# alim.net
KiCad netlist of a schematic drawn in EAGLE
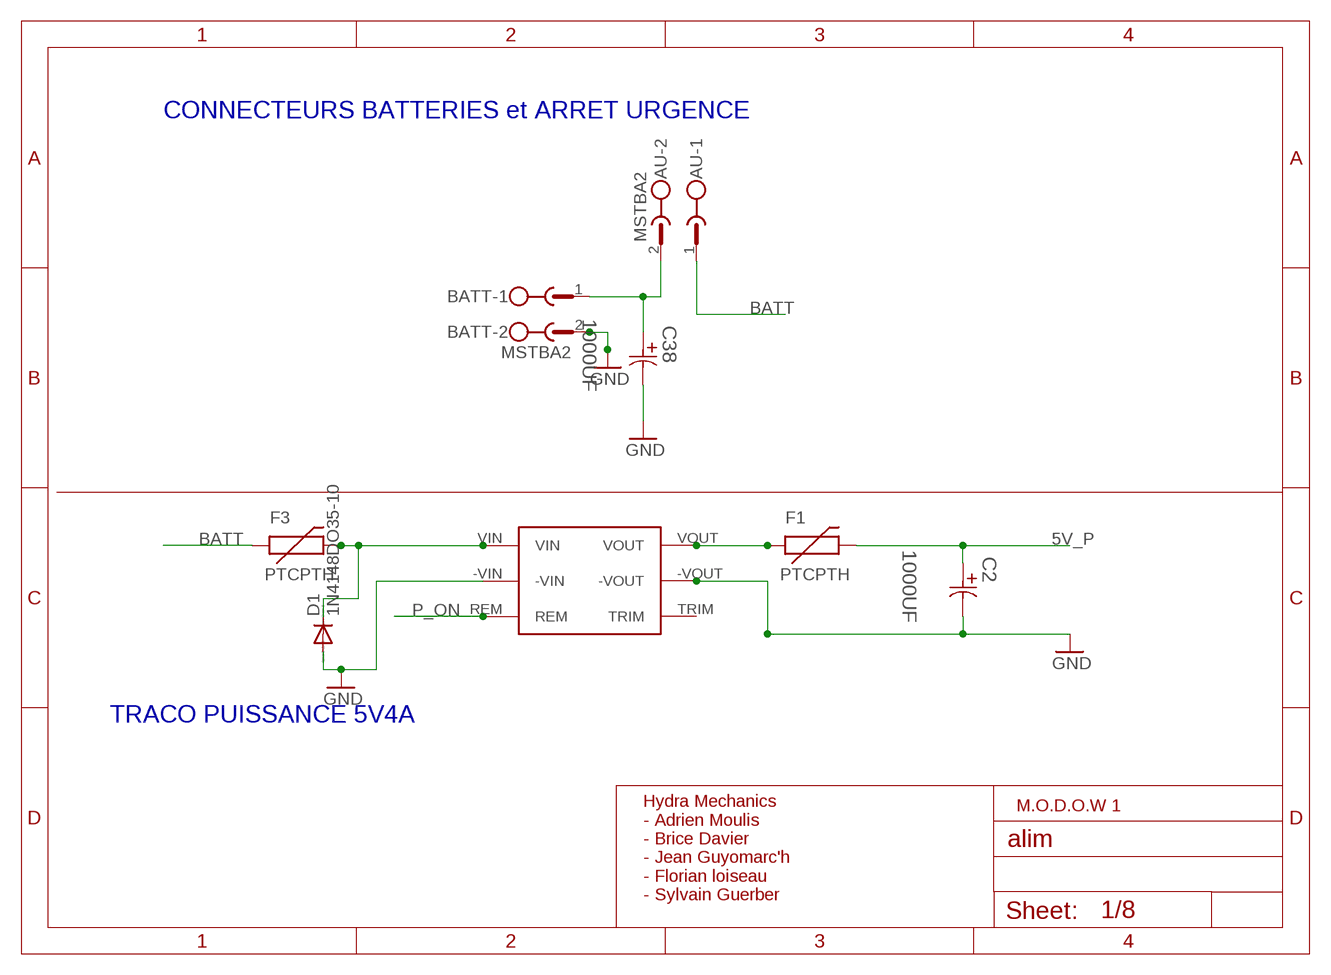
[diagram p0: schematic, sheet 1]
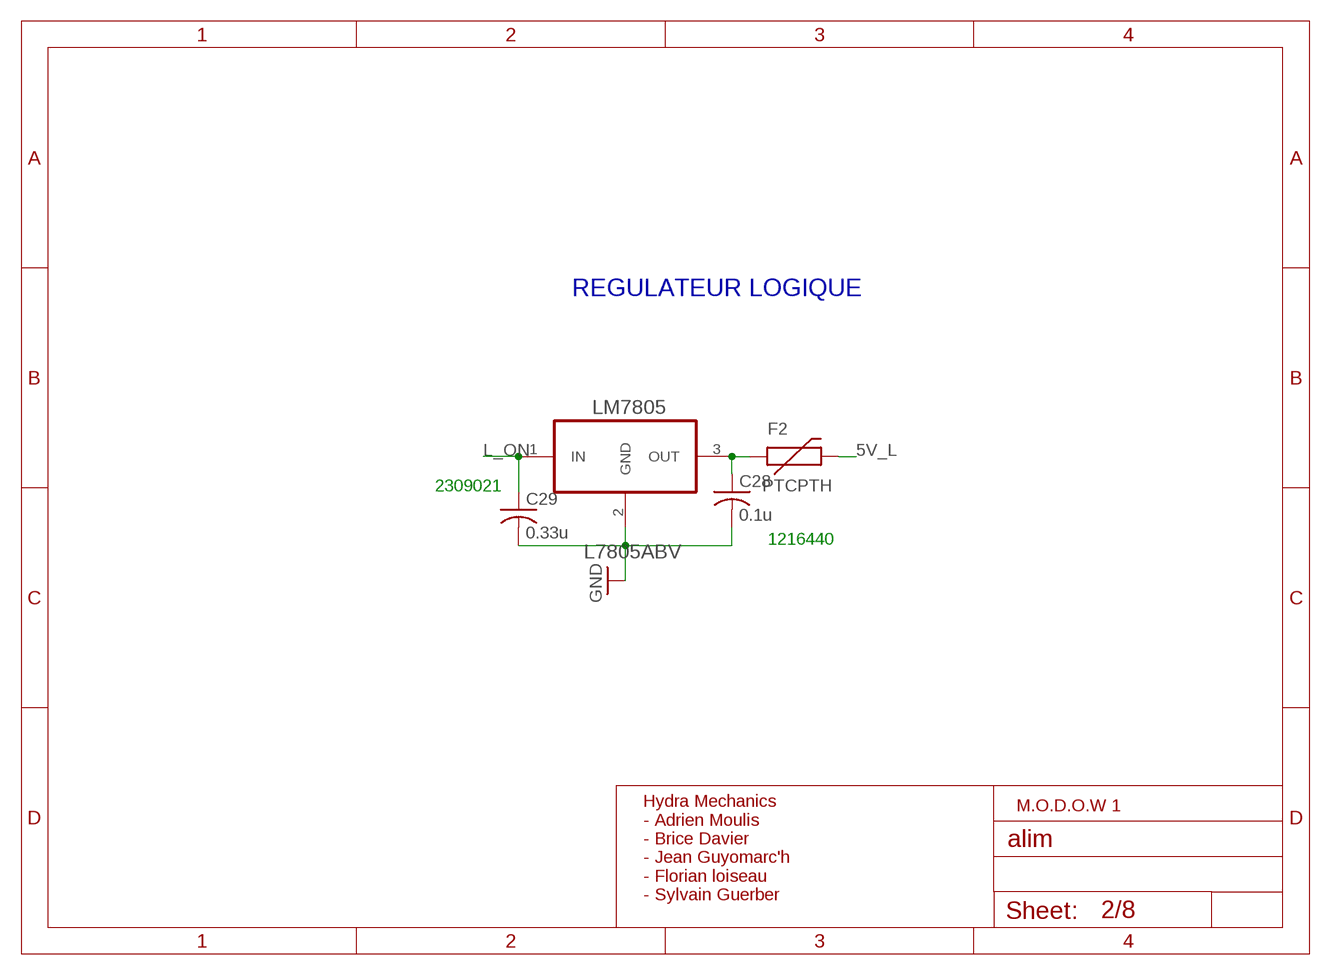
[diagram p1: schematic, sheet 2]
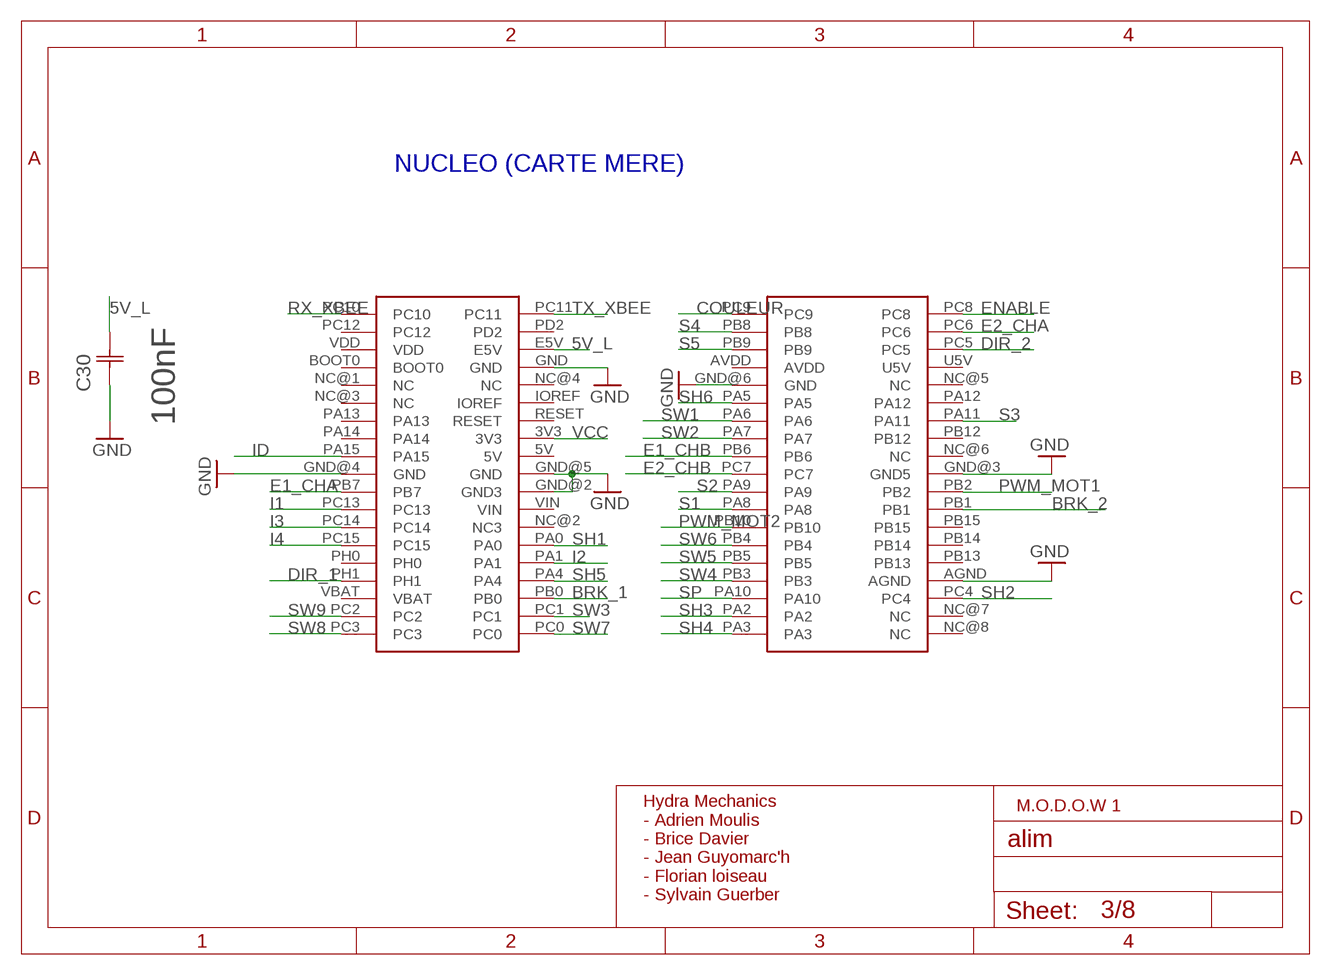
[diagram p2: schematic, sheet 3]
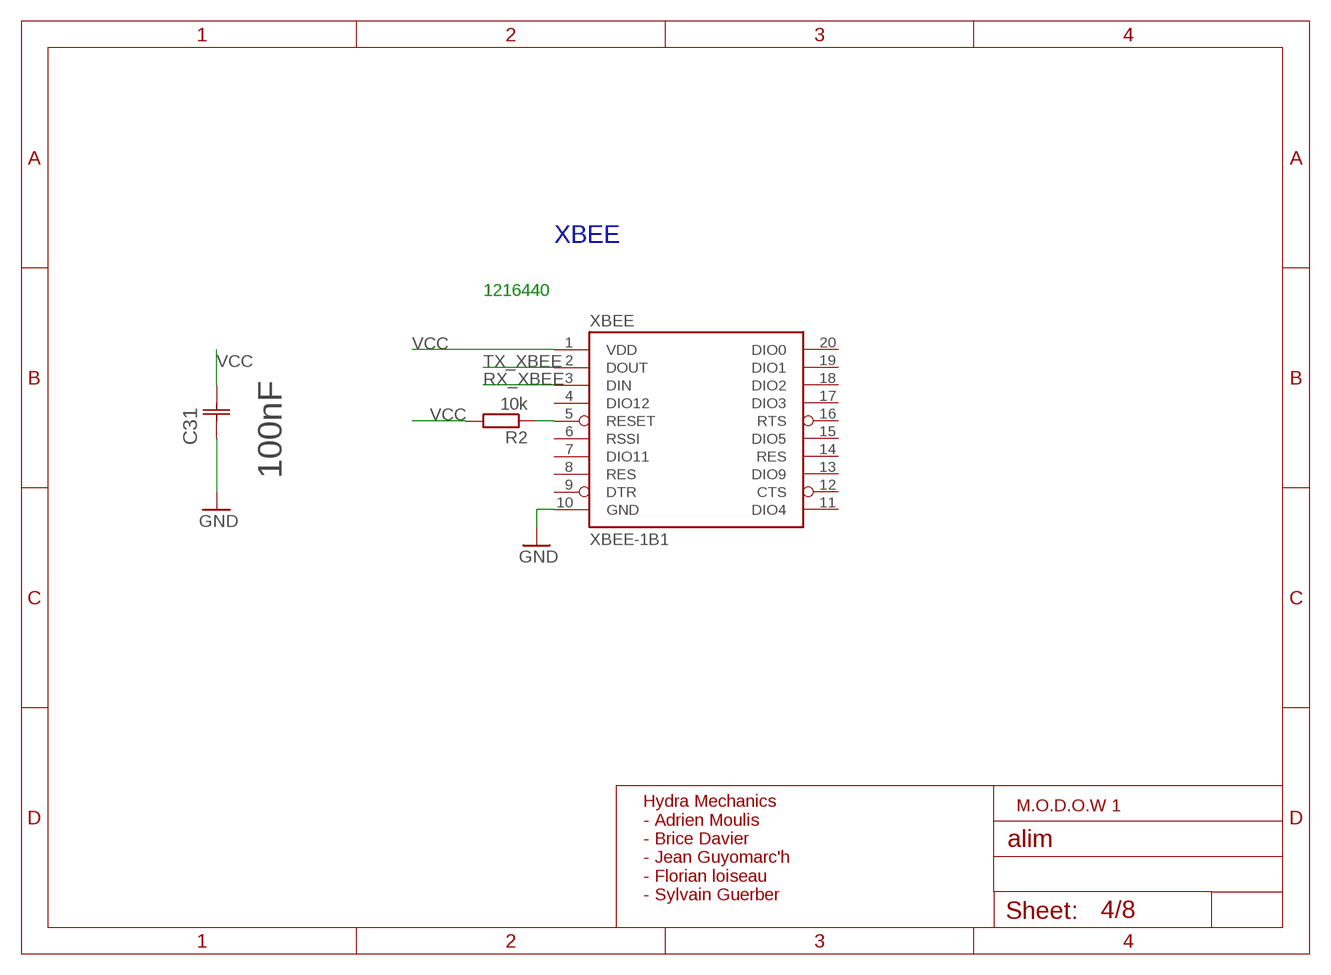
[diagram p3: schematic, sheet 4]
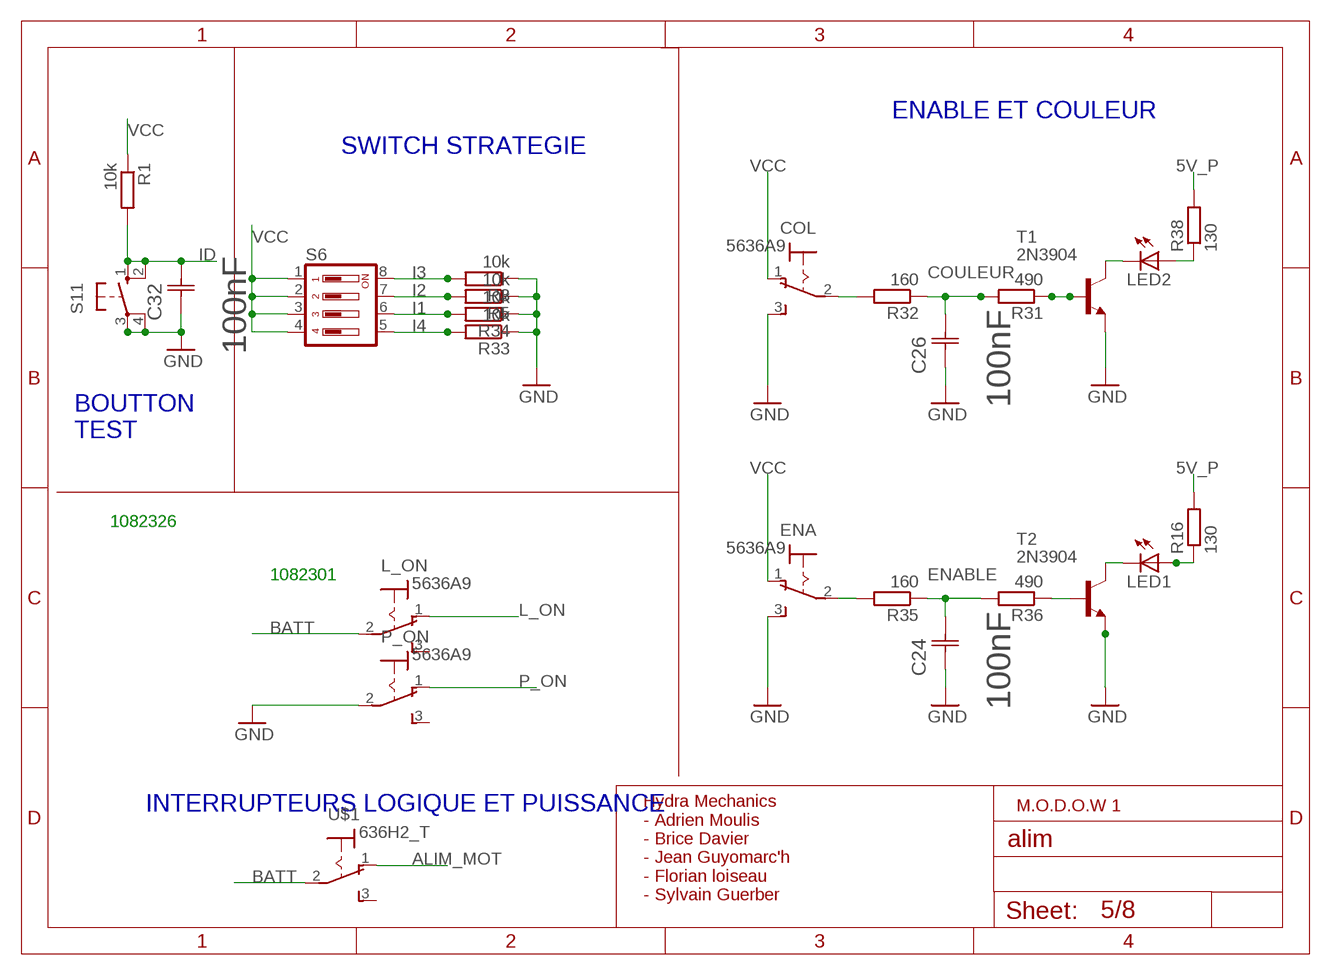
[diagram p4: schematic, sheet 5]
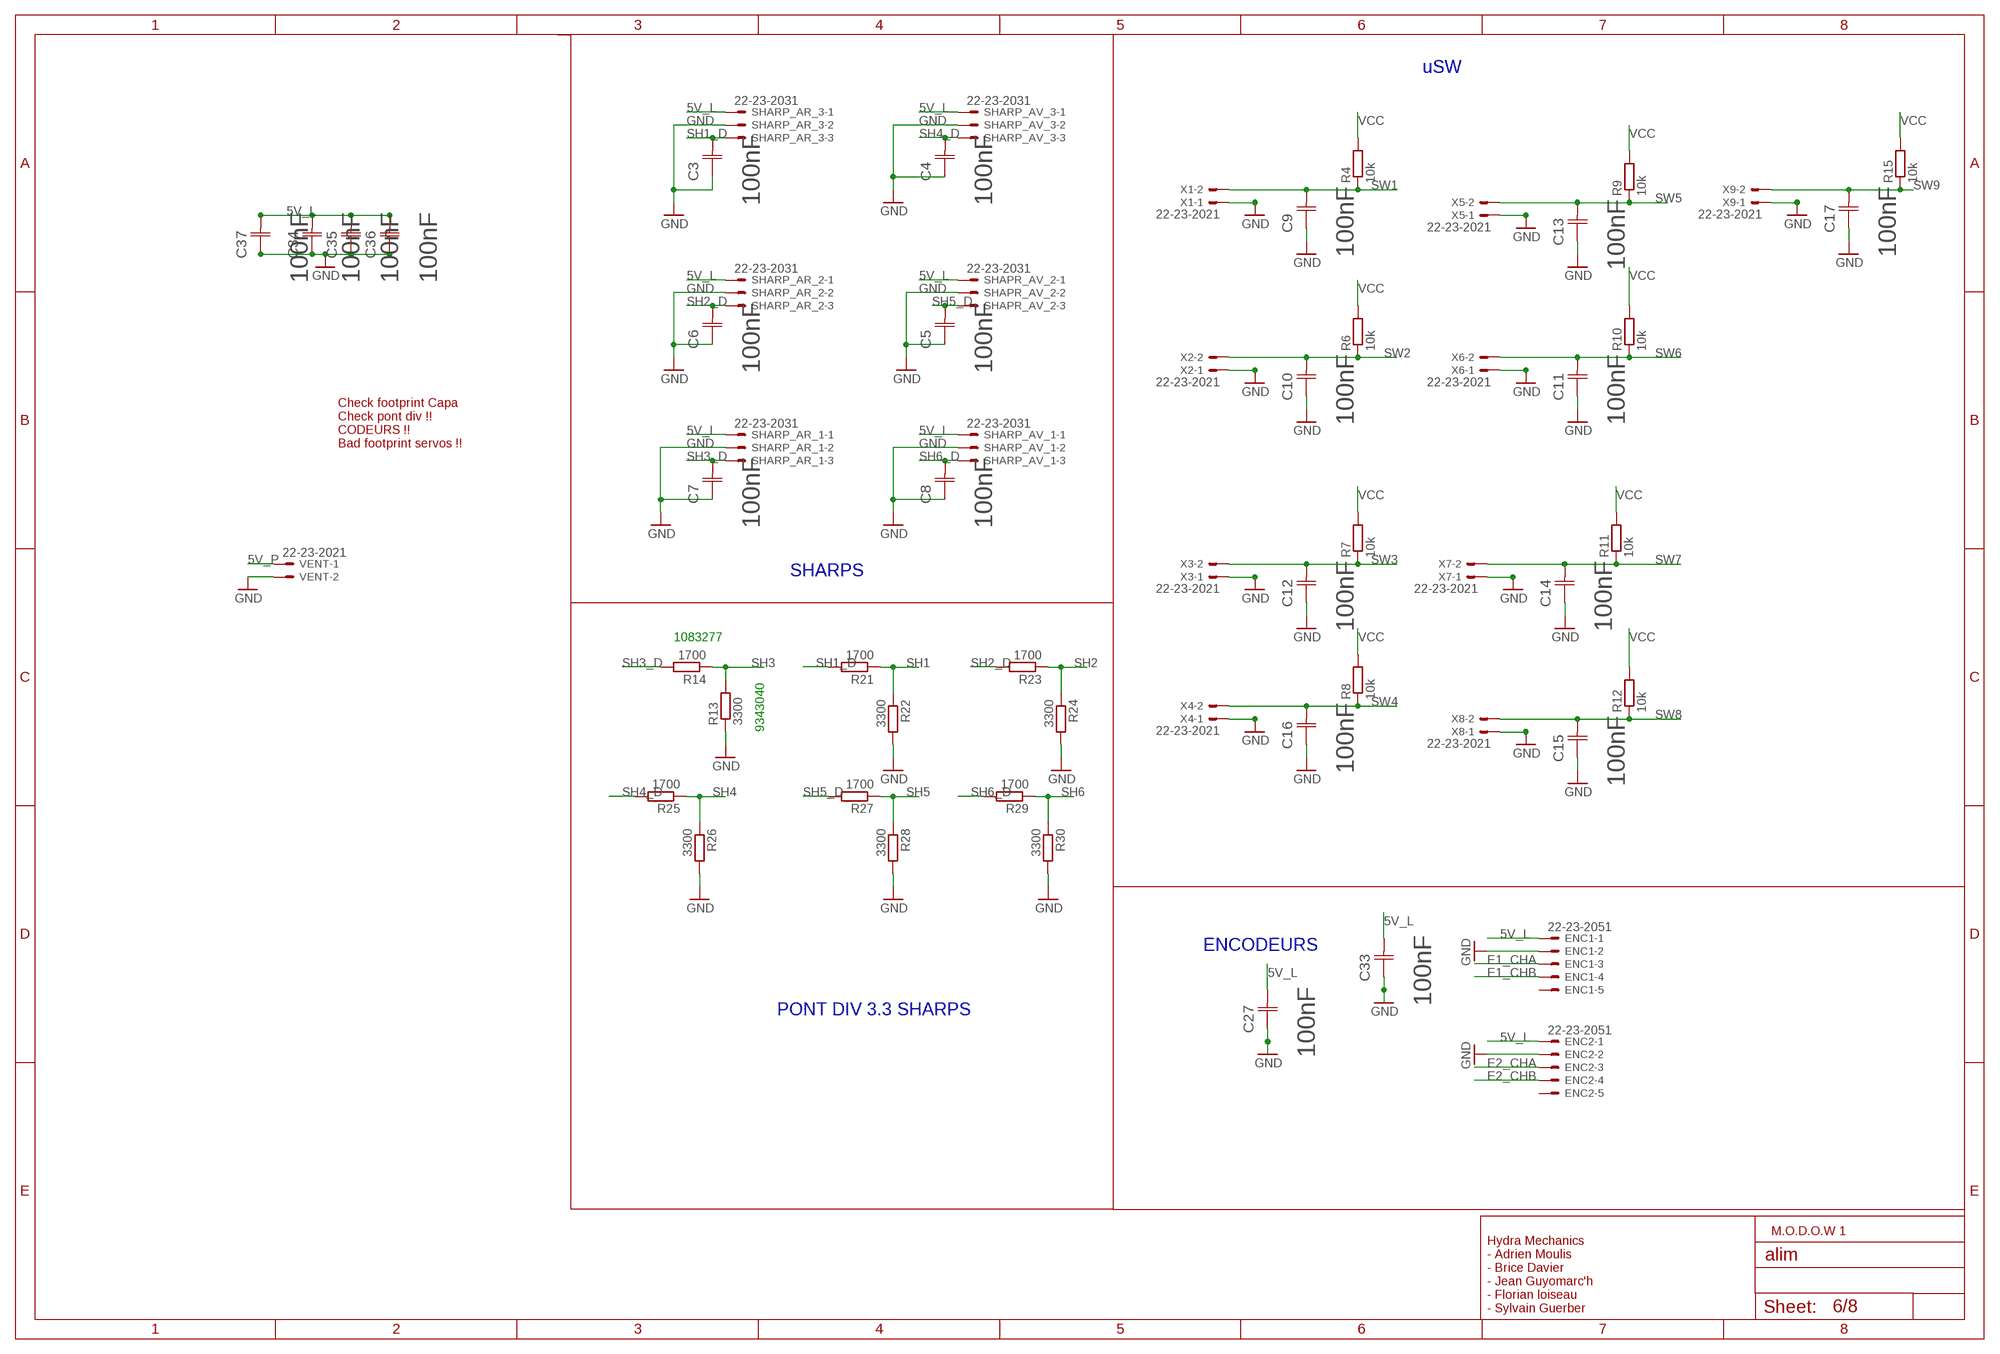
[diagram p5: schematic, sheet 6]
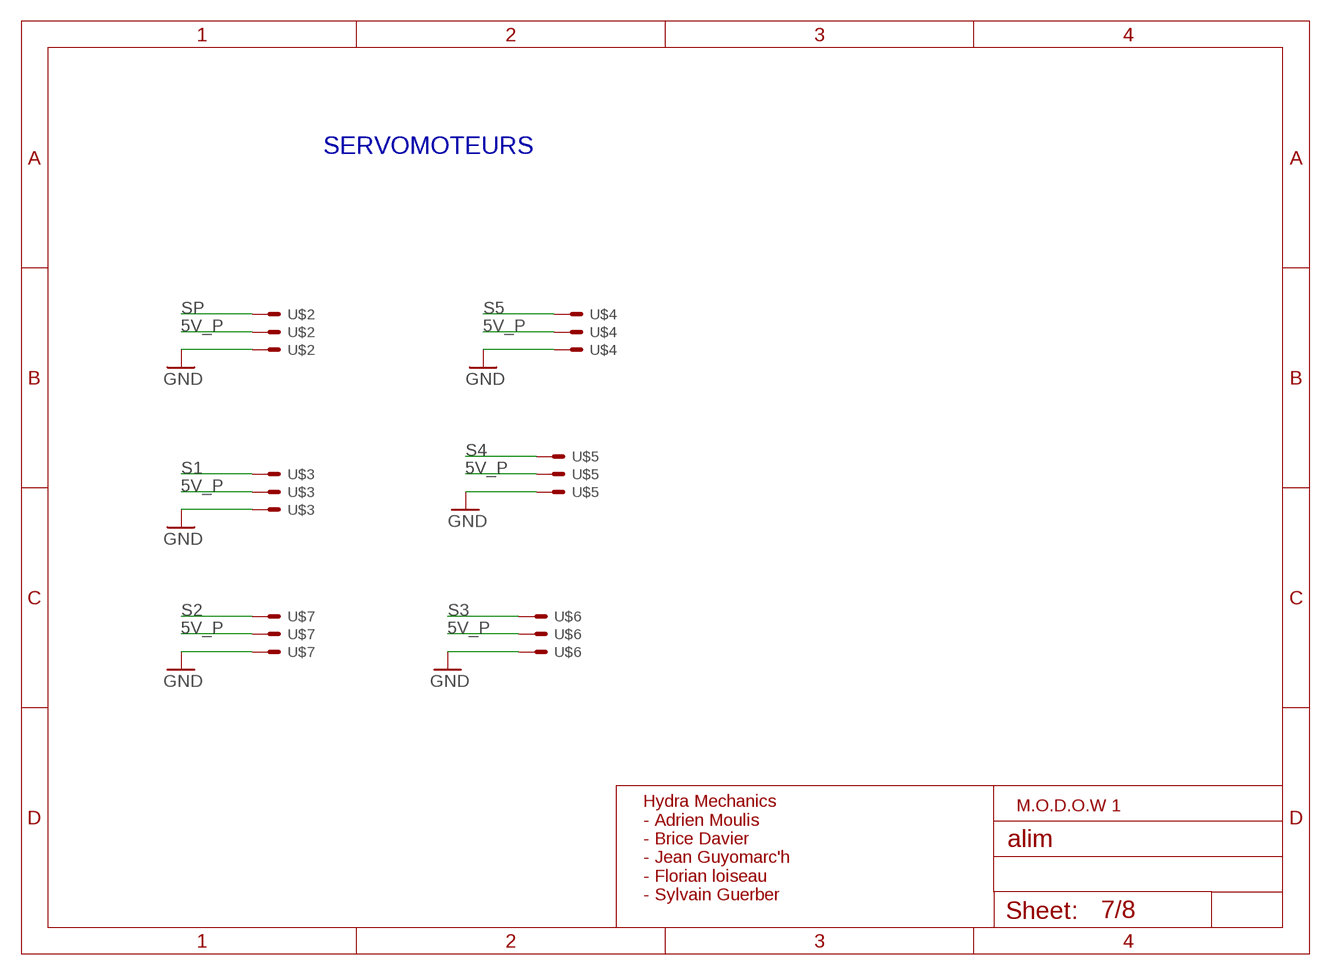
[diagram p6: schematic, sheet 7]
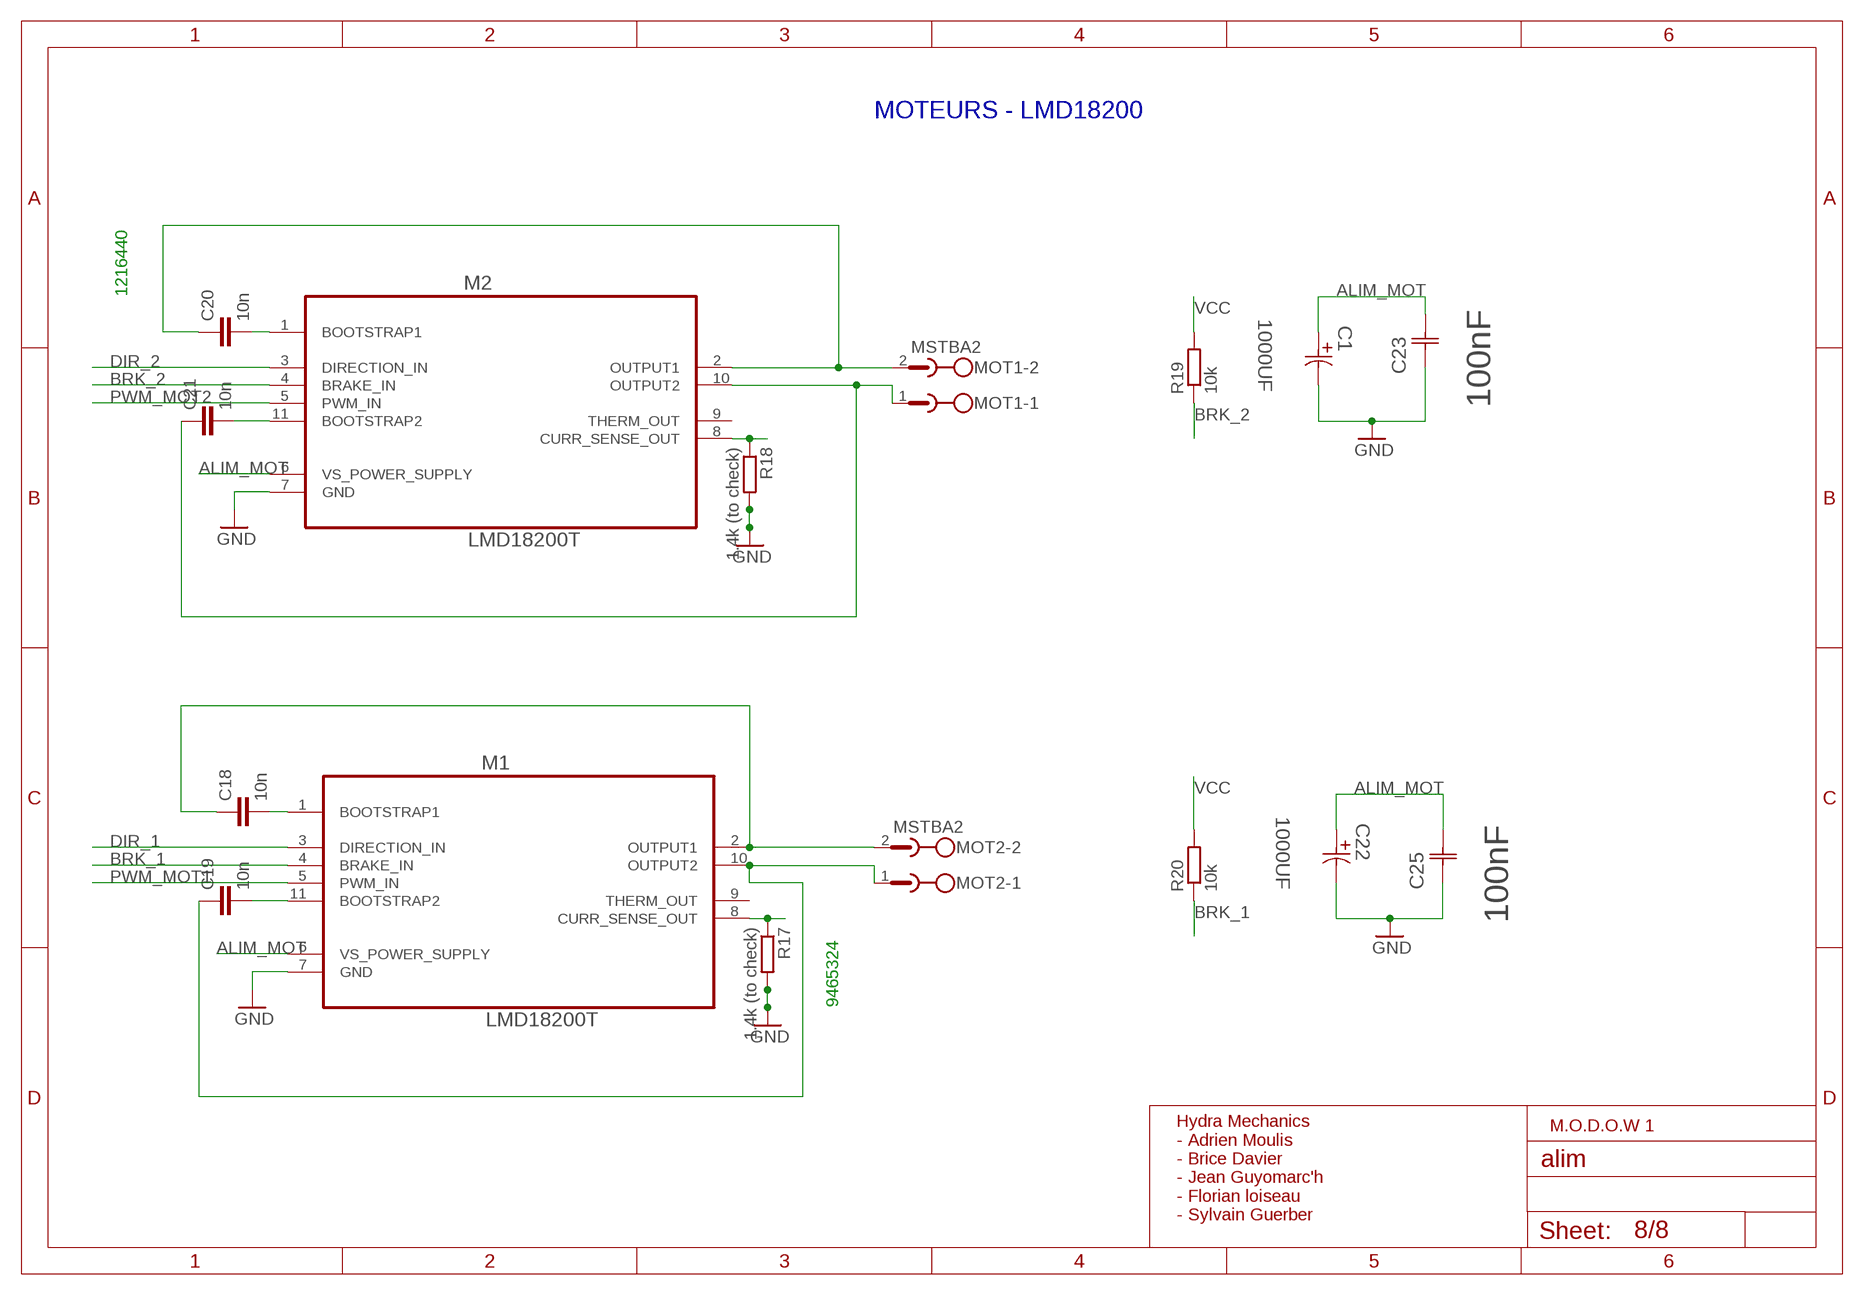
[diagram p7: schematic, sheet 8]

(export (version "E")
  (design (tool "Eeschema 10.0.6"))
  (components
    (comp (ref "U$2")
      (value "BA_HEADER_3P")
      (footprint "eagle-import:BA_HEADER_3P")
      (libsource (lib "eagle-import") (part "BA_HEADER_3P"))
    )
    (comp (ref "U$3")
      (value "BA_HEADER_3P")
      (footprint "eagle-import:BA_HEADER_3P")
      (libsource (lib "eagle-import") (part "BA_HEADER_3P"))
    )
    (comp (ref "U$4")
      (value "BA_HEADER_3P")
      (footprint "eagle-import:BA_HEADER_3P")
      (libsource (lib "eagle-import") (part "BA_HEADER_3P"))
    )
    (comp (ref "U$5")
      (value "BA_HEADER_3P")
      (footprint "eagle-import:BA_HEADER_3P")
      (libsource (lib "eagle-import") (part "BA_HEADER_3P"))
    )
    (comp (ref "U$6")
      (value "BA_HEADER_3P")
      (footprint "eagle-import:BA_HEADER_3P")
      (libsource (lib "eagle-import") (part "BA_HEADER_3P"))
    )
    (comp (ref "U$7")
      (value "BA_HEADER_3P")
      (footprint "eagle-import:BA_HEADER_3P")
      (libsource (lib "eagle-import") (part "BA_HEADER_3P"))
    )
    (comp (ref "AU")
      (value "MSTBA2")
      (footprint "eagle-import:MSTBA2")
      (fields (field (name "MF") "FARNELL") (field (name "MPN") "1757242"))
      (libsource (lib "eagle-import") (part "MSTBA2"))
    )
    (comp (ref "BATT")
      (value "MSTBA2")
      (footprint "eagle-import:MSTBA2")
      (fields (field (name "MF") "FARNELL") (field (name "MPN") "1757242"))
      (libsource (lib "eagle-import") (part "MSTBA2"))
    )
    (comp (ref "C2")
      (value "1000UF")
      (footprint "eagle-import:CAPPR500-1250X2700")
      (fields (field (name "MPN") "EEUFC1V102") (field (name "TOLERANCE") "±20 %"))
      (libsource (lib "eagle-import") (part "EEU-P5.0FC1V102"))
    )
    (comp (ref "C38")
      (value "1000UF")
      (footprint "eagle-import:CAPPR500-1250X2700")
      (fields (field (name "MPN") "EEUFC1V102") (field (name "TOLERANCE") "±20 %"))
      (libsource (lib "eagle-import") (part "EEU-P5.0FC1V102"))
    )
    (comp (ref "D1")
      (value "1N4148DO35-10")
      (footprint "eagle-import:DO35-10")
      (libsource (lib "eagle-import") (part "1N4148DO35-10"))
    )
    (comp (ref "F1")
      (value "PTCPTH")
      (footprint "eagle-import:PTC")
      (libsource (lib "eagle-import") (part "PTCPTH"))
    )
    (comp (ref "F3")
      (value "PTCPTH")
      (footprint "eagle-import:PTC")
      (libsource (lib "eagle-import") (part "PTCPTH"))
    )
    (comp (ref "U$9")
      (value "TEN202411WIN")
      (footprint "eagle-import:TEN202411WIN")
      (libsource (lib "eagle-import") (part "TEN202411WIN"))
    )
    (comp (ref "C3")
      (value "100nF")
      (footprint "eagle-import:CAPC2013X95N")
      (fields (field (name "MPN") "CC0805KRX7R9BB104") (field (name "TOLERANCE") "±10%"))
      (libsource (lib "eagle-import") (part "CC0805KRX7R9BB104"))
    )
    (comp (ref "C4")
      (value "100nF")
      (footprint "eagle-import:CAPC2013X95N")
      (fields (field (name "MPN") "CC0805KRX7R9BB104") (field (name "TOLERANCE") "±10%"))
      (libsource (lib "eagle-import") (part "CC0805KRX7R9BB104"))
    )
    (comp (ref "C5")
      (value "100nF")
      (footprint "eagle-import:CAPC2013X95N")
      (fields (field (name "MPN") "CC0805KRX7R9BB104") (field (name "TOLERANCE") "±10%"))
      (libsource (lib "eagle-import") (part "CC0805KRX7R9BB104"))
    )
    (comp (ref "C6")
      (value "100nF")
      (footprint "eagle-import:CAPC2013X95N")
      (fields (field (name "MPN") "CC0805KRX7R9BB104") (field (name "TOLERANCE") "±10%"))
      (libsource (lib "eagle-import") (part "CC0805KRX7R9BB104"))
    )
    (comp (ref "C7")
      (value "100nF")
      (footprint "eagle-import:CAPC2013X95N")
      (fields (field (name "MPN") "CC0805KRX7R9BB104") (field (name "TOLERANCE") "±10%"))
      (libsource (lib "eagle-import") (part "CC0805KRX7R9BB104"))
    )
    (comp (ref "C8")
      (value "100nF")
      (footprint "eagle-import:CAPC2013X95N")
      (fields (field (name "MPN") "CC0805KRX7R9BB104") (field (name "TOLERANCE") "±10%"))
      (libsource (lib "eagle-import") (part "CC0805KRX7R9BB104"))
    )
    (comp (ref "C9")
      (value "100nF")
      (footprint "eagle-import:CAPC2013X95N")
      (fields (field (name "MPN") "CC0805KRX7R9BB104") (field (name "TOLERANCE") "±10%"))
      (libsource (lib "eagle-import") (part "CC0805KRX7R9BB104"))
    )
    (comp (ref "C10")
      (value "100nF")
      (footprint "eagle-import:CAPC2013X95N")
      (fields (field (name "MPN") "CC0805KRX7R9BB104") (field (name "TOLERANCE") "±10%"))
      (libsource (lib "eagle-import") (part "CC0805KRX7R9BB104"))
    )
    (comp (ref "C11")
      (value "100nF")
      (footprint "eagle-import:CAPC2013X95N")
      (fields (field (name "MPN") "CC0805KRX7R9BB104") (field (name "TOLERANCE") "±10%"))
      (libsource (lib "eagle-import") (part "CC0805KRX7R9BB104"))
    )
    (comp (ref "C12")
      (value "100nF")
      (footprint "eagle-import:CAPC2013X95N")
      (fields (field (name "MPN") "CC0805KRX7R9BB104") (field (name "TOLERANCE") "±10%"))
      (libsource (lib "eagle-import") (part "CC0805KRX7R9BB104"))
    )
    (comp (ref "C13")
      (value "100nF")
      (footprint "eagle-import:CAPC2013X95N")
      (fields (field (name "MPN") "CC0805KRX7R9BB104") (field (name "TOLERANCE") "±10%"))
      (libsource (lib "eagle-import") (part "CC0805KRX7R9BB104"))
    )
    (comp (ref "C14")
      (value "100nF")
      (footprint "eagle-import:CAPC2013X95N")
      (fields (field (name "MPN") "CC0805KRX7R9BB104") (field (name "TOLERANCE") "±10%"))
      (libsource (lib "eagle-import") (part "CC0805KRX7R9BB104"))
    )
    (comp (ref "C15")
      (value "100nF")
      (footprint "eagle-import:CAPC2013X95N")
      (fields (field (name "MPN") "CC0805KRX7R9BB104") (field (name "TOLERANCE") "±10%"))
      (libsource (lib "eagle-import") (part "CC0805KRX7R9BB104"))
    )
    (comp (ref "C16")
      (value "100nF")
      (footprint "eagle-import:CAPC2013X95N")
      (fields (field (name "MPN") "CC0805KRX7R9BB104") (field (name "TOLERANCE") "±10%"))
      (libsource (lib "eagle-import") (part "CC0805KRX7R9BB104"))
    )
    (comp (ref "C17")
      (value "100nF")
      (footprint "eagle-import:CAPC2013X95N")
      (fields (field (name "MPN") "CC0805KRX7R9BB104") (field (name "TOLERANCE") "±10%"))
      (libsource (lib "eagle-import") (part "CC0805KRX7R9BB104"))
    )
    (comp (ref "C27")
      (value "100nF")
      (footprint "eagle-import:CAPC2013X95N")
      (fields (field (name "MPN") "CC0805KRX7R9BB104") (field (name "TOLERANCE") "±10%"))
      (libsource (lib "eagle-import") (part "CC0805KRX7R9BB104"))
    )
    (comp (ref "C33")
      (value "100nF")
      (footprint "eagle-import:CAPC2013X95N")
      (fields (field (name "MPN") "CC0805KRX7R9BB104") (field (name "TOLERANCE") "±10%"))
      (libsource (lib "eagle-import") (part "CC0805KRX7R9BB104"))
    )
    (comp (ref "C34")
      (value "100nF")
      (footprint "eagle-import:CAPC2013X95N")
      (fields (field (name "MPN") "CC0805KRX7R9BB104") (field (name "TOLERANCE") "±10%"))
      (libsource (lib "eagle-import") (part "CC0805KRX7R9BB104"))
    )
    (comp (ref "C35")
      (value "100nF")
      (footprint "eagle-import:CAPC2013X95N")
      (fields (field (name "MPN") "CC0805KRX7R9BB104") (field (name "TOLERANCE") "±10%"))
      (libsource (lib "eagle-import") (part "CC0805KRX7R9BB104"))
    )
    (comp (ref "C36")
      (value "100nF")
      (footprint "eagle-import:CAPC2013X95N")
      (fields (field (name "MPN") "CC0805KRX7R9BB104") (field (name "TOLERANCE") "±10%"))
      (libsource (lib "eagle-import") (part "CC0805KRX7R9BB104"))
    )
    (comp (ref "C37")
      (value "100nF")
      (footprint "eagle-import:CAPC2013X95N")
      (fields (field (name "MPN") "CC0805KRX7R9BB104") (field (name "TOLERANCE") "±10%"))
      (libsource (lib "eagle-import") (part "CC0805KRX7R9BB104"))
    )
    (comp (ref "ENC1")
      (value "22-23-2051")
      (footprint "eagle-import:22-23-2051")
      (fields (field (name "MF") "MOLEX"))
      (libsource (lib "eagle-import") (part "22-23-2051"))
    )
    (comp (ref "ENC2")
      (value "22-23-2051")
      (footprint "eagle-import:22-23-2051")
      (fields (field (name "MF") "MOLEX"))
      (libsource (lib "eagle-import") (part "22-23-2051"))
    )
    (comp (ref "R4")
      (value "10k")
      (footprint "eagle-import:0207_7")
      (libsource (lib "eagle-import") (part "R-EU_0207/7"))
    )
    (comp (ref "R6")
      (value "10k")
      (footprint "eagle-import:0207_7")
      (libsource (lib "eagle-import") (part "R-EU_0207/7"))
    )
    (comp (ref "R7")
      (value "10k")
      (footprint "eagle-import:0207_7")
      (libsource (lib "eagle-import") (part "R-EU_0207/7"))
    )
    (comp (ref "R8")
      (value "10k")
      (footprint "eagle-import:0207_7")
      (libsource (lib "eagle-import") (part "R-EU_0207/7"))
    )
    (comp (ref "R9")
      (value "10k")
      (footprint "eagle-import:0207_7")
      (libsource (lib "eagle-import") (part "R-EU_0207/7"))
    )
    (comp (ref "R10")
      (value "10k")
      (footprint "eagle-import:0207_7")
      (libsource (lib "eagle-import") (part "R-EU_0207/7"))
    )
    (comp (ref "R11")
      (value "10k")
      (footprint "eagle-import:0207_7")
      (libsource (lib "eagle-import") (part "R-EU_0207/7"))
    )
    (comp (ref "R12")
      (value "10k")
      (footprint "eagle-import:0207_7")
      (libsource (lib "eagle-import") (part "R-EU_0207/7"))
    )
    (comp (ref "R13")
      (value "3300")
      (footprint "eagle-import:0207_7")
      (libsource (lib "eagle-import") (part "R-EU_0207/7"))
    )
    (comp (ref "R14")
      (value "1700")
      (footprint "eagle-import:0207_7")
      (libsource (lib "eagle-import") (part "R-EU_0207/7"))
    )
    (comp (ref "R15")
      (value "10k")
      (footprint "eagle-import:0207_7")
      (libsource (lib "eagle-import") (part "R-EU_0207/7"))
    )
    (comp (ref "R21")
      (value "1700")
      (footprint "eagle-import:0207_7")
      (libsource (lib "eagle-import") (part "R-EU_0207/7"))
    )
    (comp (ref "R22")
      (value "3300")
      (footprint "eagle-import:0207_7")
      (libsource (lib "eagle-import") (part "R-EU_0207/7"))
    )
    (comp (ref "R23")
      (value "1700")
      (footprint "eagle-import:0207_7")
      (libsource (lib "eagle-import") (part "R-EU_0207/7"))
    )
    (comp (ref "R24")
      (value "3300")
      (footprint "eagle-import:0207_7")
      (libsource (lib "eagle-import") (part "R-EU_0207/7"))
    )
    (comp (ref "R25")
      (value "1700")
      (footprint "eagle-import:0207_7")
      (libsource (lib "eagle-import") (part "R-EU_0207/7"))
    )
    (comp (ref "R26")
      (value "3300")
      (footprint "eagle-import:0207_7")
      (libsource (lib "eagle-import") (part "R-EU_0207/7"))
    )
    (comp (ref "R27")
      (value "1700")
      (footprint "eagle-import:0207_7")
      (libsource (lib "eagle-import") (part "R-EU_0207/7"))
    )
    (comp (ref "R28")
      (value "3300")
      (footprint "eagle-import:0207_7")
      (libsource (lib "eagle-import") (part "R-EU_0207/7"))
    )
    (comp (ref "R29")
      (value "1700")
      (footprint "eagle-import:0207_7")
      (libsource (lib "eagle-import") (part "R-EU_0207/7"))
    )
    (comp (ref "R30")
      (value "3300")
      (footprint "eagle-import:0207_7")
      (libsource (lib "eagle-import") (part "R-EU_0207/7"))
    )
    (comp (ref "SHAPR_AV_2")
      (value "22-23-2031")
      (footprint "eagle-import:22-23-2031")
      (fields (field (name "MF") "MOLEX"))
      (libsource (lib "eagle-import") (part "22-23-2031"))
    )
    (comp (ref "SHARP_AR_1")
      (value "22-23-2031")
      (footprint "eagle-import:22-23-2031")
      (fields (field (name "MF") "MOLEX"))
      (libsource (lib "eagle-import") (part "22-23-2031"))
    )
    (comp (ref "SHARP_AR_2")
      (value "22-23-2031")
      (footprint "eagle-import:22-23-2031")
      (fields (field (name "MF") "MOLEX"))
      (libsource (lib "eagle-import") (part "22-23-2031"))
    )
    (comp (ref "SHARP_AR_3")
      (value "22-23-2031")
      (footprint "eagle-import:22-23-2031")
      (fields (field (name "MF") "MOLEX"))
      (libsource (lib "eagle-import") (part "22-23-2031"))
    )
    (comp (ref "SHARP_AV_1")
      (value "22-23-2031")
      (footprint "eagle-import:22-23-2031")
      (fields (field (name "MF") "MOLEX"))
      (libsource (lib "eagle-import") (part "22-23-2031"))
    )
    (comp (ref "SHARP_AV_3")
      (value "22-23-2031")
      (footprint "eagle-import:22-23-2031")
      (fields (field (name "MF") "MOLEX"))
      (libsource (lib "eagle-import") (part "22-23-2031"))
    )
    (comp (ref "VENT")
      (value "22-23-2021")
      (footprint "eagle-import:22-23-2021")
      (fields (field (name "MF") "MOLEX"))
      (libsource (lib "eagle-import") (part "22-23-2021"))
    )
    (comp (ref "X1")
      (value "22-23-2021")
      (footprint "eagle-import:22-23-2021")
      (fields (field (name "MF") "MOLEX"))
      (libsource (lib "eagle-import") (part "22-23-2021"))
    )
    (comp (ref "X2")
      (value "22-23-2021")
      (footprint "eagle-import:22-23-2021")
      (fields (field (name "MF") "MOLEX"))
      (libsource (lib "eagle-import") (part "22-23-2021"))
    )
    (comp (ref "X3")
      (value "22-23-2021")
      (footprint "eagle-import:22-23-2021")
      (fields (field (name "MF") "MOLEX"))
      (libsource (lib "eagle-import") (part "22-23-2021"))
    )
    (comp (ref "X4")
      (value "22-23-2021")
      (footprint "eagle-import:22-23-2021")
      (fields (field (name "MF") "MOLEX"))
      (libsource (lib "eagle-import") (part "22-23-2021"))
    )
    (comp (ref "X5")
      (value "22-23-2021")
      (footprint "eagle-import:22-23-2021")
      (fields (field (name "MF") "MOLEX"))
      (libsource (lib "eagle-import") (part "22-23-2021"))
    )
    (comp (ref "X6")
      (value "22-23-2021")
      (footprint "eagle-import:22-23-2021")
      (fields (field (name "MF") "MOLEX"))
      (libsource (lib "eagle-import") (part "22-23-2021"))
    )
    (comp (ref "X7")
      (value "22-23-2021")
      (footprint "eagle-import:22-23-2021")
      (fields (field (name "MF") "MOLEX"))
      (libsource (lib "eagle-import") (part "22-23-2021"))
    )
    (comp (ref "X8")
      (value "22-23-2021")
      (footprint "eagle-import:22-23-2021")
      (fields (field (name "MF") "MOLEX"))
      (libsource (lib "eagle-import") (part "22-23-2021"))
    )
    (comp (ref "X9")
      (value "22-23-2021")
      (footprint "eagle-import:22-23-2021")
      (fields (field (name "MF") "MOLEX"))
      (libsource (lib "eagle-import") (part "22-23-2021"))
    )
    (comp (ref "C24")
      (value "100nF")
      (footprint "eagle-import:CAPC2013X95N")
      (fields (field (name "MPN") "CC0805KRX7R9BB104") (field (name "TOLERANCE") "±10%"))
      (libsource (lib "eagle-import") (part "CC0805KRX7R9BB104"))
    )
    (comp (ref "C26")
      (value "100nF")
      (footprint "eagle-import:CAPC2013X95N")
      (fields (field (name "MPN") "CC0805KRX7R9BB104") (field (name "TOLERANCE") "±10%"))
      (libsource (lib "eagle-import") (part "CC0805KRX7R9BB104"))
    )
    (comp (ref "C32")
      (value "100nF")
      (footprint "eagle-import:CAPC2013X95N")
      (fields (field (name "MPN") "CC0805KRX7R9BB104") (field (name "TOLERANCE") "±10%"))
      (libsource (lib "eagle-import") (part "CC0805KRX7R9BB104"))
    )
    (comp (ref "COL")
      (value "5636A9")
      (footprint "eagle-import:5636A9")
      (libsource (lib "eagle-import") (part "5636A9"))
    )
    (comp (ref "ENA")
      (value "5636A9")
      (footprint "eagle-import:5636A9")
      (libsource (lib "eagle-import") (part "5636A9"))
    )
    (comp (ref "LED1")
      (value "LED3MM")
      (footprint "eagle-import:LED3MM")
      (libsource (lib "eagle-import") (part "LED3MM"))
    )
    (comp (ref "LED2")
      (value "LED3MM")
      (footprint "eagle-import:LED3MM")
      (libsource (lib "eagle-import") (part "LED3MM"))
    )
    (comp (ref "L_ON")
      (value "5636A9")
      (footprint "eagle-import:5636A9")
      (libsource (lib "eagle-import") (part "5636A9"))
    )
    (comp (ref "P_ON")
      (value "5636A9")
      (footprint "eagle-import:5636A9")
      (libsource (lib "eagle-import") (part "5636A9"))
    )
    (comp (ref "R1")
      (value "10k")
      (footprint "eagle-import:0207_7")
      (libsource (lib "eagle-import") (part "R-EU_0207/7"))
    )
    (comp (ref "R3")
      (value "10k")
      (footprint "eagle-import:0207_7")
      (libsource (lib "eagle-import") (part "R-EU_0207/7"))
    )
    (comp (ref "R5")
      (value "10k")
      (footprint "eagle-import:0207_7")
      (libsource (lib "eagle-import") (part "R-EU_0207/7"))
    )
    (comp (ref "R16")
      (value "130")
      (footprint "eagle-import:0207_7")
      (libsource (lib "eagle-import") (part "R-EU_0207/7"))
    )
    (comp (ref "R31")
      (value "490")
      (footprint "eagle-import:0207_7")
      (libsource (lib "eagle-import") (part "R-EU_0207/7"))
    )
    (comp (ref "R32")
      (value "160")
      (footprint "eagle-import:0207_7")
      (libsource (lib "eagle-import") (part "R-EU_0207/7"))
    )
    (comp (ref "R33")
      (value "10k")
      (footprint "eagle-import:0207_7")
      (libsource (lib "eagle-import") (part "R-EU_0207/7"))
    )
    (comp (ref "R34")
      (value "10k")
      (footprint "eagle-import:0207_7")
      (libsource (lib "eagle-import") (part "R-EU_0207/7"))
    )
    (comp (ref "R35")
      (value "160")
      (footprint "eagle-import:0207_7")
      (libsource (lib "eagle-import") (part "R-EU_0207/7"))
    )
    (comp (ref "R36")
      (value "490")
      (footprint "eagle-import:0207_7")
      (libsource (lib "eagle-import") (part "R-EU_0207/7"))
    )
    (comp (ref "R38")
      (value "130")
      (footprint "eagle-import:0207_7")
      (libsource (lib "eagle-import") (part "R-EU_0207/7"))
    )
    (comp (ref "S6")
      (value "DS04")
      (footprint "eagle-import:DS-04")
      (libsource (lib "eagle-import") (part "DS04"))
    )
    (comp (ref "S11")
      (value "10-XX")
      (footprint "eagle-import:B3F-10XX")
      (fields (field (name "MPN") "B3F-1000"))
      (libsource (lib "eagle-import") (part "10-XX"))
    )
    (comp (ref "T1")
      (value "2N3904")
      (footprint "eagle-import:TO92")
      (libsource (lib "eagle-import") (part "2N3904"))
    )
    (comp (ref "T2")
      (value "2N3904")
      (footprint "eagle-import:TO92")
      (libsource (lib "eagle-import") (part "2N3904"))
    )
    (comp (ref "U$1")
      (value "636H2_T")
      (footprint "eagle-import:636H2")
      (libsource (lib "eagle-import") (part "636H2_T"))
    )
    (comp (ref "C28")
      (value "0.1u")
      (footprint "eagle-import:C0805")
      (libsource (lib "eagle-import") (part "C-USC0805"))
    )
    (comp (ref "C29")
      (value "0.33u")
      (footprint "eagle-import:C0805")
      (libsource (lib "eagle-import") (part "C-USC0805"))
    )
    (comp (ref "F2")
      (value "PTCPTH")
      (footprint "eagle-import:PTC")
      (libsource (lib "eagle-import") (part "PTCPTH"))
    )
    (comp (ref "LM7805")
      (value "L7805ABV")
      (footprint "eagle-import:TO254P482X1024X3124-3P")
      (libsource (lib "eagle-import") (part "L7805ABV"))
    )
    (comp (ref "C1")
      (value "1000UF")
      (footprint "eagle-import:CAPPR500-1250X2700")
      (fields (field (name "MPN") "EEUFC1V102") (field (name "TOLERANCE") "±20 %"))
      (libsource (lib "eagle-import") (part "EEU-P5.0FC1V102"))
    )
    (comp (ref "C18")
      (value "10n")
      (footprint "eagle-import:C025-024X044")
      (libsource (lib "eagle-import") (part "C-EU025-024X044"))
    )
    (comp (ref "C19")
      (value "10n")
      (footprint "eagle-import:C025-024X044")
      (libsource (lib "eagle-import") (part "C-EU025-024X044"))
    )
    (comp (ref "C20")
      (value "10n")
      (footprint "eagle-import:C025-024X044")
      (libsource (lib "eagle-import") (part "C-EU025-024X044"))
    )
    (comp (ref "C21")
      (value "10n")
      (footprint "eagle-import:C025-024X044")
      (libsource (lib "eagle-import") (part "C-EU025-024X044"))
    )
    (comp (ref "C22")
      (value "1000UF")
      (footprint "eagle-import:CAPPR500-1250X2700")
      (fields (field (name "MPN") "EEUFC1V102") (field (name "TOLERANCE") "±20 %"))
      (libsource (lib "eagle-import") (part "EEU-P5.0FC1V102"))
    )
    (comp (ref "C23")
      (value "100nF")
      (footprint "eagle-import:CAPC2013X95N")
      (fields (field (name "MPN") "CC0805KRX7R9BB104") (field (name "TOLERANCE") "±10%"))
      (libsource (lib "eagle-import") (part "CC0805KRX7R9BB104"))
    )
    (comp (ref "C25")
      (value "100nF")
      (footprint "eagle-import:CAPC2013X95N")
      (fields (field (name "MPN") "CC0805KRX7R9BB104") (field (name "TOLERANCE") "±10%"))
      (libsource (lib "eagle-import") (part "CC0805KRX7R9BB104"))
    )
    (comp (ref "M1")
      (value "LMD18200T")
      (footprint "eagle-import:DIOB_LMD18200T")
      (libsource (lib "eagle-import") (part "LMD18200T"))
    )
    (comp (ref "M2")
      (value "LMD18200T")
      (footprint "eagle-import:DIOB_LMD18200T")
      (libsource (lib "eagle-import") (part "LMD18200T"))
    )
    (comp (ref "MOT1")
      (value "MSTBA2")
      (footprint "eagle-import:MSTBA2")
      (fields (field (name "MF") "FARNELL") (field (name "MPN") "1757242"))
      (libsource (lib "eagle-import") (part "MSTBA2"))
    )
    (comp (ref "MOT2")
      (value "MSTBA2")
      (footprint "eagle-import:MSTBA2")
      (fields (field (name "MF") "FARNELL") (field (name "MPN") "1757242"))
      (libsource (lib "eagle-import") (part "MSTBA2"))
    )
    (comp (ref "R17")
      (value "1.4k (to check)")
      (footprint "eagle-import:0207_7")
      (libsource (lib "eagle-import") (part "R-EU_0207/7"))
    )
    (comp (ref "R18")
      (value "1.4k (to check)")
      (footprint "eagle-import:0207_7")
      (libsource (lib "eagle-import") (part "R-EU_0207/7"))
    )
    (comp (ref "R19")
      (value "10k")
      (footprint "eagle-import:0207_7")
      (libsource (lib "eagle-import") (part "R-EU_0207/7"))
    )
    (comp (ref "R20")
      (value "10k")
      (footprint "eagle-import:0207_7")
      (libsource (lib "eagle-import") (part "R-EU_0207/7"))
    )
    (comp (ref "C30")
      (value "100nF")
      (footprint "eagle-import:CAPC2013X95N")
      (fields (field (name "MPN") "CC0805KRX7R9BB104") (field (name "TOLERANCE") "±10%"))
      (libsource (lib "eagle-import") (part "CC0805KRX7R9BB104"))
    )
    (comp (ref "NUCLEO")
      (value "NUCLEO-F446-RE-CON")
      (footprint "eagle-import:NUCLEO-F446RE-CON")
      (libsource (lib "eagle-import") (part "NUCLEO-F446-RE-CON"))
    )
    (comp (ref "C31")
      (value "100nF")
      (footprint "eagle-import:CAPC2013X95N")
      (fields (field (name "MPN") "CC0805KRX7R9BB104") (field (name "TOLERANCE") "±10%"))
      (libsource (lib "eagle-import") (part "CC0805KRX7R9BB104"))
    )
    (comp (ref "R2")
      (value "10k")
      (footprint "eagle-import:0207_7")
      (libsource (lib "eagle-import") (part "R-EU_0207/7"))
    )
    (comp (ref "XBEE")
      (value "XBEE-1B1")
      (footprint "eagle-import:XBEE-1")
      (libsource (lib "eagle-import") (part "XBEE-1B1"))
    )
  )
  (nets
    (net (code "1") (name "5V_L") (class "Default")
      (node (ref "C27") (pin "2") (pinfunction "C2_2") (pintype "passive"))
      (node (ref "C30") (pin "2") (pinfunction "C2_2") (pintype "passive"))
      (node (ref "C33") (pin "2") (pinfunction "C2_2") (pintype "passive"))
      (node (ref "C34") (pin "2") (pinfunction "C2_2") (pintype "passive"))
      (node (ref "C35") (pin "2") (pinfunction "C2_2") (pintype "passive"))
      (node (ref "C36") (pin "2") (pinfunction "C2_2") (pintype "passive"))
      (node (ref "C37") (pin "2") (pinfunction "C2_2") (pintype "passive"))
      (node (ref "ENC1") (pin "1") (pinfunction "S_1") (pintype "passive"))
      (node (ref "ENC2") (pin "1") (pinfunction "S_1") (pintype "passive"))
      (node (ref "F2") (pin "P$2") (pinfunction "2_P$2") (pintype "bidirectional"))
      (node (ref "NUCLEO") (pin "E5V") (pinfunction "E5V_E5V") (pintype "bidirectional"))
      (node (ref "SHAPR_AV_2") (pin "1") (pinfunction "S_1") (pintype "passive"))
      (node (ref "SHARP_AR_1") (pin "1") (pinfunction "S_1") (pintype "passive"))
      (node (ref "SHARP_AR_2") (pin "1") (pinfunction "S_1") (pintype "passive"))
      (node (ref "SHARP_AR_3") (pin "1") (pinfunction "S_1") (pintype "passive"))
      (node (ref "SHARP_AV_1") (pin "1") (pinfunction "S_1") (pintype "passive"))
      (node (ref "SHARP_AV_3") (pin "1") (pinfunction "S_1") (pintype "passive"))
    )
    (net (code "2") (name "5V_P") (class "Default")
      (node (ref "C2") (pin "1") (pinfunction "1_1") (pintype "passive"))
      (node (ref "F1") (pin "P$2") (pinfunction "2_P$2") (pintype "bidirectional"))
      (node (ref "R16") (pin "2") (pinfunction "2_2") (pintype "passive"))
      (node (ref "R38") (pin "2") (pinfunction "2_2") (pintype "passive"))
      (node (ref "U$2") (pin "P$2") (pinfunction "S2_P$2") (pintype "passive"))
      (node (ref "U$3") (pin "P$2") (pinfunction "S2_P$2") (pintype "passive"))
      (node (ref "U$4") (pin "P$2") (pinfunction "S2_P$2") (pintype "passive"))
      (node (ref "U$5") (pin "P$2") (pinfunction "S2_P$2") (pintype "passive"))
      (node (ref "U$6") (pin "P$2") (pinfunction "S2_P$2") (pintype "passive"))
      (node (ref "U$7") (pin "P$2") (pinfunction "S2_P$2") (pintype "passive"))
      (node (ref "VENT") (pin "1") (pinfunction "S_1") (pintype "passive"))
    )
    (net (code "3") (name "ALIM_MOT") (class "Default")
      (node (ref "C1") (pin "1") (pinfunction "1_1") (pintype "passive"))
      (node (ref "C22") (pin "1") (pinfunction "1_1") (pintype "passive"))
      (node (ref "C23") (pin "2") (pinfunction "C2_2") (pintype "passive"))
      (node (ref "C25") (pin "2") (pinfunction "C2_2") (pintype "passive"))
      (node (ref "M1") (pin "6") (pinfunction "VS_POWER_SUPPLY_6") (pintype "power_in"))
      (node (ref "M2") (pin "6") (pinfunction "VS_POWER_SUPPLY_6") (pintype "power_in"))
      (node (ref "U$1") (pin "1") (pinfunction "O_1") (pintype "passive"))
    )
    (net (code "4") (name "BATT") (class "Default")
      (node (ref "AU") (pin "1") (pinfunction "1_1") (pintype "passive"))
      (node (ref "F3") (pin "P$1") (pinfunction "1_P$1") (pintype "bidirectional"))
      (node (ref "L_ON") (pin "2") (pinfunction "P_2") (pintype "passive"))
      (node (ref "U$1") (pin "2") (pinfunction "P_2") (pintype "passive"))
    )
    (net (code "5") (name "BRK_1") (class "Default")
      (node (ref "M1") (pin "4") (pinfunction "BRAKE_IN_4") (pintype "input"))
      (node (ref "NUCLEO") (pin "PB0") (pinfunction "PB0_PB0") (pintype "bidirectional"))
      (node (ref "R20") (pin "1") (pinfunction "1_1") (pintype "passive"))
    )
    (net (code "6") (name "BRK_2") (class "Default")
      (node (ref "M2") (pin "4") (pinfunction "BRAKE_IN_4") (pintype "input"))
      (node (ref "NUCLEO") (pin "PB1") (pinfunction "PB1_PB1") (pintype "bidirectional"))
      (node (ref "R19") (pin "1") (pinfunction "1_1") (pintype "passive"))
    )
    (net (code "7") (name "COULEUR") (class "Default")
      (node (ref "C26") (pin "2") (pinfunction "C2_2") (pintype "passive"))
      (node (ref "NUCLEO") (pin "PC9") (pinfunction "PC9_PC9") (pintype "bidirectional"))
      (node (ref "R31") (pin "2") (pinfunction "2_2") (pintype "passive"))
      (node (ref "R32") (pin "1") (pinfunction "1_1") (pintype "passive"))
    )
    (net (code "8") (name "DIR_1") (class "Default")
      (node (ref "M1") (pin "3") (pinfunction "DIRECTION_IN_3") (pintype "input"))
      (node (ref "NUCLEO") (pin "PH1") (pinfunction "PH1_PH1") (pintype "bidirectional"))
    )
    (net (code "9") (name "DIR_2") (class "Default")
      (node (ref "M2") (pin "3") (pinfunction "DIRECTION_IN_3") (pintype "input"))
      (node (ref "NUCLEO") (pin "PC5") (pinfunction "PC5_PC5") (pintype "bidirectional"))
    )
    (net (code "10") (name "E1_CHA") (class "Default")
      (node (ref "ENC1") (pin "3") (pinfunction "S_3") (pintype "passive"))
      (node (ref "NUCLEO") (pin "PB7") (pinfunction "PB7_PB7") (pintype "bidirectional"))
    )
    (net (code "11") (name "E1_CHB") (class "Default")
      (node (ref "ENC1") (pin "4") (pinfunction "S_4") (pintype "passive"))
      (node (ref "NUCLEO") (pin "PB6") (pinfunction "PB6_PB6") (pintype "bidirectional"))
    )
    (net (code "12") (name "E2_CHA") (class "Default")
      (node (ref "ENC2") (pin "3") (pinfunction "S_3") (pintype "passive"))
      (node (ref "NUCLEO") (pin "PC6") (pinfunction "PC6_PC6") (pintype "bidirectional"))
    )
    (net (code "13") (name "E2_CHB") (class "Default")
      (node (ref "ENC2") (pin "4") (pinfunction "S_4") (pintype "passive"))
      (node (ref "NUCLEO") (pin "PC7") (pinfunction "PC7_PC7") (pintype "bidirectional"))
    )
    (net (code "14") (name "ENABLE") (class "Default")
      (node (ref "C24") (pin "2") (pinfunction "C2_2") (pintype "passive"))
      (node (ref "NUCLEO") (pin "PC8") (pinfunction "PC8_PC8") (pintype "bidirectional"))
      (node (ref "R35") (pin "1") (pinfunction "1_1") (pintype "passive"))
      (node (ref "R36") (pin "2") (pinfunction "2_2") (pintype "passive"))
    )
    (net (code "15") (name "GND") (class "Default")
      (node (ref "BATT") (pin "2") (pinfunction "1_2") (pintype "passive"))
      (node (ref "C1") (pin "2") (pinfunction "2_2") (pintype "passive"))
      (node (ref "C10") (pin "1") (pinfunction "C1_1") (pintype "passive"))
      (node (ref "C11") (pin "1") (pinfunction "C1_1") (pintype "passive"))
      (node (ref "C12") (pin "1") (pinfunction "C1_1") (pintype "passive"))
      (node (ref "C13") (pin "1") (pinfunction "C1_1") (pintype "passive"))
      (node (ref "C14") (pin "1") (pinfunction "C1_1") (pintype "passive"))
      (node (ref "C15") (pin "1") (pinfunction "C1_1") (pintype "passive"))
      (node (ref "C16") (pin "1") (pinfunction "C1_1") (pintype "passive"))
      (node (ref "C17") (pin "1") (pinfunction "C1_1") (pintype "passive"))
      (node (ref "C2") (pin "2") (pinfunction "2_2") (pintype "passive"))
      (node (ref "C22") (pin "2") (pinfunction "2_2") (pintype "passive"))
      (node (ref "C23") (pin "1") (pinfunction "C1_1") (pintype "passive"))
      (node (ref "C24") (pin "1") (pinfunction "C1_1") (pintype "passive"))
      (node (ref "C25") (pin "1") (pinfunction "C1_1") (pintype "passive"))
      (node (ref "C26") (pin "1") (pinfunction "C1_1") (pintype "passive"))
      (node (ref "C27") (pin "1") (pinfunction "C1_1") (pintype "passive"))
      (node (ref "C28") (pin "2") (pinfunction "2_2") (pintype "passive"))
      (node (ref "C29") (pin "2") (pinfunction "2_2") (pintype "passive"))
      (node (ref "C3") (pin "1") (pinfunction "C1_1") (pintype "passive"))
      (node (ref "C30") (pin "1") (pinfunction "C1_1") (pintype "passive"))
      (node (ref "C31") (pin "1") (pinfunction "C1_1") (pintype "passive"))
      (node (ref "C32") (pin "1") (pinfunction "C1_1") (pintype "passive"))
      (node (ref "C33") (pin "1") (pinfunction "C1_1") (pintype "passive"))
      (node (ref "C34") (pin "1") (pinfunction "C1_1") (pintype "passive"))
      (node (ref "C35") (pin "1") (pinfunction "C1_1") (pintype "passive"))
      (node (ref "C36") (pin "1") (pinfunction "C1_1") (pintype "passive"))
      (node (ref "C37") (pin "1") (pinfunction "C1_1") (pintype "passive"))
      (node (ref "C38") (pin "2") (pinfunction "2_2") (pintype "passive"))
      (node (ref "C4") (pin "1") (pinfunction "C1_1") (pintype "passive"))
      (node (ref "C5") (pin "1") (pinfunction "C1_1") (pintype "passive"))
      (node (ref "C6") (pin "1") (pinfunction "C1_1") (pintype "passive"))
      (node (ref "C7") (pin "1") (pinfunction "C1_1") (pintype "passive"))
      (node (ref "C8") (pin "1") (pinfunction "C1_1") (pintype "passive"))
      (node (ref "C9") (pin "1") (pinfunction "C1_1") (pintype "passive"))
      (node (ref "COL") (pin "3") (pinfunction "S_3") (pintype "passive"))
      (node (ref "D1") (pin "A") (pinfunction "A_A") (pintype "passive"))
      (node (ref "ENA") (pin "3") (pinfunction "S_3") (pintype "passive"))
      (node (ref "ENC1") (pin "2") (pinfunction "S_2") (pintype "passive"))
      (node (ref "ENC2") (pin "2") (pinfunction "S_2") (pintype "passive"))
      (node (ref "LM7805") (pin "2") (pinfunction "GND_2") (pintype "passive"))
      (node (ref "M1") (pin "7") (pinfunction "GND_7") (pintype "passive"))
      (node (ref "M2") (pin "7") (pinfunction "GND_7") (pintype "passive"))
      (node (ref "NUCLEO") (pin "AGND") (pinfunction "AGND_AGND") (pintype "bidirectional"))
      (node (ref "NUCLEO") (pin "GND") (pinfunction "GND_GND") (pintype "bidirectional"))
      (node (ref "NUCLEO") (pin "GND@2") (pinfunction "GND3_GND@2") (pintype "bidirectional"))
      (node (ref "NUCLEO") (pin "GND@3") (pinfunction "GND5_GND@3") (pintype "bidirectional"))
      (node (ref "NUCLEO") (pin "GND@4") (pinfunction "GND_GND@4") (pintype "bidirectional"))
      (node (ref "NUCLEO") (pin "GND@5") (pinfunction "GND_GND@5") (pintype "bidirectional"))
      (node (ref "NUCLEO") (pin "GND@6") (pinfunction "GND_GND@6") (pintype "bidirectional"))
      (node (ref "P_ON") (pin "2") (pinfunction "P_2") (pintype "passive"))
      (node (ref "R13") (pin "1") (pinfunction "1_1") (pintype "passive"))
      (node (ref "R17") (pin "2") (pinfunction "2_2") (pintype "passive"))
      (node (ref "R18") (pin "2") (pinfunction "2_2") (pintype "passive"))
      (node (ref "R22") (pin "2") (pinfunction "2_2") (pintype "passive"))
      (node (ref "R24") (pin "2") (pinfunction "2_2") (pintype "passive"))
      (node (ref "R26") (pin "2") (pinfunction "2_2") (pintype "passive"))
      (node (ref "R28") (pin "2") (pinfunction "2_2") (pintype "passive"))
      (node (ref "R3") (pin "1") (pinfunction "1_1") (pintype "passive"))
      (node (ref "R30") (pin "2") (pinfunction "2_2") (pintype "passive"))
      (node (ref "R33") (pin "1") (pinfunction "1_1") (pintype "passive"))
      (node (ref "R34") (pin "1") (pinfunction "1_1") (pintype "passive"))
      (node (ref "R5") (pin "1") (pinfunction "1_1") (pintype "passive"))
      (node (ref "S11") (pin "3") (pinfunction "P_3") (pintype "passive"))
      (node (ref "S11") (pin "4") (pinfunction "P1_4") (pintype "passive"))
      (node (ref "SHAPR_AV_2") (pin "2") (pinfunction "S_2") (pintype "passive"))
      (node (ref "SHARP_AR_1") (pin "2") (pinfunction "S_2") (pintype "passive"))
      (node (ref "SHARP_AR_2") (pin "2") (pinfunction "S_2") (pintype "passive"))
      (node (ref "SHARP_AR_3") (pin "2") (pinfunction "S_2") (pintype "passive"))
      (node (ref "SHARP_AV_1") (pin "2") (pinfunction "S_2") (pintype "passive"))
      (node (ref "SHARP_AV_3") (pin "2") (pinfunction "S_2") (pintype "passive"))
      (node (ref "T1") (pin "3") (pinfunction "E_3") (pintype "passive"))
      (node (ref "T2") (pin "3") (pinfunction "E_3") (pintype "passive"))
      (node (ref "U$2") (pin "P$3") (pinfunction "S3_P$3") (pintype "passive"))
      (node (ref "U$3") (pin "P$3") (pinfunction "S3_P$3") (pintype "passive"))
      (node (ref "U$4") (pin "P$3") (pinfunction "S3_P$3") (pintype "passive"))
      (node (ref "U$5") (pin "P$3") (pinfunction "S3_P$3") (pintype "passive"))
      (node (ref "U$6") (pin "P$3") (pinfunction "S3_P$3") (pintype "passive"))
      (node (ref "U$7") (pin "P$3") (pinfunction "S3_P$3") (pintype "passive"))
      (node (ref "U$9") (pin "-VIN") (pinfunction "-VIN_-VIN") (pintype "bidirectional"))
      (node (ref "U$9") (pin "-VOUT") (pinfunction "-VOUT_-VOUT") (pintype "bidirectional"))
      (node (ref "VENT") (pin "2") (pinfunction "S_2") (pintype "passive"))
      (node (ref "X1") (pin "1") (pinfunction "S_1") (pintype "passive"))
      (node (ref "X2") (pin "1") (pinfunction "S_1") (pintype "passive"))
      (node (ref "X3") (pin "1") (pinfunction "S_1") (pintype "passive"))
      (node (ref "X4") (pin "1") (pinfunction "S_1") (pintype "passive"))
      (node (ref "X5") (pin "1") (pinfunction "S_1") (pintype "passive"))
      (node (ref "X6") (pin "1") (pinfunction "S_1") (pintype "passive"))
      (node (ref "X7") (pin "1") (pinfunction "S_1") (pintype "passive"))
      (node (ref "X8") (pin "1") (pinfunction "S_1") (pintype "passive"))
      (node (ref "X9") (pin "1") (pinfunction "S_1") (pintype "passive"))
      (node (ref "XBEE") (pin "10") (pinfunction "GND_10") (pintype "power_in"))
    )
    (net (code "16") (name "I1") (class "Default")
      (node (ref "NUCLEO") (pin "PC13") (pinfunction "PC13_PC13") (pintype "bidirectional"))
      (node (ref "R34") (pin "2") (pinfunction "2_2") (pintype "passive"))
      (node (ref "S6") (pin "6") (pinfunction "6_6") (pintype "passive"))
    )
    (net (code "17") (name "I2") (class "Default")
      (node (ref "NUCLEO") (pin "PA1") (pinfunction "PA1_PA1") (pintype "bidirectional"))
      (node (ref "R5") (pin "2") (pinfunction "2_2") (pintype "passive"))
      (node (ref "S6") (pin "7") (pinfunction "7_7") (pintype "passive"))
    )
    (net (code "18") (name "I3") (class "Default")
      (node (ref "NUCLEO") (pin "PC14") (pinfunction "PC14_PC14") (pintype "bidirectional"))
      (node (ref "R3") (pin "2") (pinfunction "2_2") (pintype "passive"))
      (node (ref "S6") (pin "8") (pinfunction "8_8") (pintype "passive"))
    )
    (net (code "19") (name "I4") (class "Default")
      (node (ref "NUCLEO") (pin "PC15") (pinfunction "PC15_PC15") (pintype "bidirectional"))
      (node (ref "R33") (pin "2") (pinfunction "2_2") (pintype "passive"))
      (node (ref "S6") (pin "5") (pinfunction "5_5") (pintype "passive"))
    )
    (net (code "20") (name "ID") (class "Default")
      (node (ref "C32") (pin "2") (pinfunction "C2_2") (pintype "passive"))
      (node (ref "NUCLEO") (pin "PA15") (pinfunction "PA15_PA15") (pintype "bidirectional"))
      (node (ref "R1") (pin "2") (pinfunction "2_2") (pintype "passive"))
      (node (ref "S11") (pin "1") (pinfunction "S_1") (pintype "passive"))
      (node (ref "S11") (pin "2") (pinfunction "S1_2") (pintype "passive"))
    )
    (net (code "21") (name "L_ON") (class "Default")
      (node (ref "C29") (pin "1") (pinfunction "1_1") (pintype "passive"))
      (node (ref "LM7805") (pin "1") (pinfunction "IN_1") (pintype "input"))
      (node (ref "L_ON") (pin "1") (pinfunction "O_1") (pintype "passive"))
    )
    (net (code "22") (name "Net-(AUB-1)") (class "Default")
      (node (ref "AU") (pin "2") (pinfunction "1_2") (pintype "passive"))
      (node (ref "BATT") (pin "1") (pinfunction "1_1") (pintype "passive"))
      (node (ref "C38") (pin "1") (pinfunction "1_1") (pintype "passive"))
    )
    (net (code "23") (name "Net-(COL-P)") (class "Default")
      (node (ref "COL") (pin "2") (pinfunction "P_2") (pintype "passive"))
      (node (ref "R32") (pin "2") (pinfunction "2_2") (pintype "passive"))
    )
    (net (code "24") (name "Net-(ENA-P)") (class "Default")
      (node (ref "ENA") (pin "2") (pinfunction "P_2") (pintype "passive"))
      (node (ref "R35") (pin "2") (pinfunction "2_2") (pintype "passive"))
    )
    (net (code "25") (name "Net-(F1-1)") (class "Default")
      (node (ref "F1") (pin "P$1") (pinfunction "1_P$1") (pintype "bidirectional"))
      (node (ref "U$9") (pin "VOUT") (pinfunction "VOUT_VOUT") (pintype "bidirectional"))
    )
    (net (code "26") (name "Net-(F2-1)") (class "Default")
      (node (ref "C28") (pin "1") (pinfunction "1_1") (pintype "passive"))
      (node (ref "F2") (pin "P$1") (pinfunction "1_P$1") (pintype "bidirectional"))
      (node (ref "LM7805") (pin "3") (pinfunction "OUT_3") (pintype "output"))
    )
    (net (code "27") (name "Net-(F3-2)") (class "Default")
      (node (ref "D1") (pin "C") (pinfunction "C_C") (pintype "passive"))
      (node (ref "F3") (pin "P$2") (pinfunction "2_P$2") (pintype "bidirectional"))
      (node (ref "U$9") (pin "VIN") (pinfunction "VIN_VIN") (pintype "bidirectional"))
    )
    (net (code "28") (name "Net-(LED1-C)") (class "Default")
      (node (ref "LED1") (pin "K") (pinfunction "C_K") (pintype "passive"))
      (node (ref "T2") (pin "1") (pinfunction "C_1") (pintype "passive"))
    )
    (net (code "29") (name "Net-(LED1-PadA)") (class "Default")
      (node (ref "LED1") (pin "A") (pinfunction "A_A") (pintype "passive"))
      (node (ref "R16") (pin "1") (pinfunction "1_1") (pintype "passive"))
    )
    (net (code "30") (name "Net-(LED2-C)") (class "Default")
      (node (ref "LED2") (pin "K") (pinfunction "C_K") (pintype "passive"))
      (node (ref "T1") (pin "1") (pinfunction "C_1") (pintype "passive"))
    )
    (net (code "31") (name "Net-(LED2-PadA)") (class "Default")
      (node (ref "LED2") (pin "A") (pinfunction "A_A") (pintype "passive"))
      (node (ref "R38") (pin "1") (pinfunction "1_1") (pintype "passive"))
    )
    (net (code "32") (name "Net-(M1-BOOTSTRAP1)") (class "Default")
      (node (ref "C18") (pin "2") (pinfunction "2_2") (pintype "passive"))
      (node (ref "M1") (pin "1") (pinfunction "BOOTSTRAP1_1") (pintype "input"))
    )
    (net (code "33") (name "Net-(M1-BOOTSTRAP2)") (class "Default")
      (node (ref "C19") (pin "2") (pinfunction "2_2") (pintype "passive"))
      (node (ref "M1") (pin "11") (pinfunction "BOOTSTRAP2_11") (pintype "input"))
    )
    (net (code "34") (name "Net-(M1-CURR_SENSE_OUT)") (class "Default")
      (node (ref "M1") (pin "8") (pinfunction "CURR_SENSE_OUT_8") (pintype "output"))
      (node (ref "R17") (pin "1") (pinfunction "1_1") (pintype "passive"))
    )
    (net (code "35") (name "Net-(M1-OUTPUT1)") (class "Default")
      (node (ref "C18") (pin "1") (pinfunction "1_1") (pintype "passive"))
      (node (ref "M1") (pin "2") (pinfunction "OUTPUT1_2") (pintype "input"))
      (node (ref "MOT2") (pin "2") (pinfunction "1_2") (pintype "passive"))
    )
    (net (code "36") (name "Net-(M1-OUTPUT2)") (class "Default")
      (node (ref "C19") (pin "1") (pinfunction "1_1") (pintype "passive"))
      (node (ref "M1") (pin "10") (pinfunction "OUTPUT2_10") (pintype "output"))
      (node (ref "MOT2") (pin "1") (pinfunction "1_1") (pintype "passive"))
    )
    (net (code "37") (name "Net-(M2-BOOTSTRAP1)") (class "Default")
      (node (ref "C20") (pin "2") (pinfunction "2_2") (pintype "passive"))
      (node (ref "M2") (pin "1") (pinfunction "BOOTSTRAP1_1") (pintype "input"))
    )
    (net (code "38") (name "Net-(M2-BOOTSTRAP2)") (class "Default")
      (node (ref "C21") (pin "2") (pinfunction "2_2") (pintype "passive"))
      (node (ref "M2") (pin "11") (pinfunction "BOOTSTRAP2_11") (pintype "input"))
    )
    (net (code "39") (name "Net-(M2-CURR_SENSE_OUT)") (class "Default")
      (node (ref "M2") (pin "8") (pinfunction "CURR_SENSE_OUT_8") (pintype "output"))
      (node (ref "R18") (pin "1") (pinfunction "1_1") (pintype "passive"))
    )
    (net (code "40") (name "Net-(M2-OUTPUT1)") (class "Default")
      (node (ref "C20") (pin "1") (pinfunction "1_1") (pintype "passive"))
      (node (ref "M2") (pin "2") (pinfunction "OUTPUT1_2") (pintype "input"))
      (node (ref "MOT1") (pin "2") (pinfunction "1_2") (pintype "passive"))
    )
    (net (code "41") (name "Net-(M2-OUTPUT2)") (class "Default")
      (node (ref "C21") (pin "1") (pinfunction "1_1") (pintype "passive"))
      (node (ref "M2") (pin "10") (pinfunction "OUTPUT2_10") (pintype "output"))
      (node (ref "MOT1") (pin "1") (pinfunction "1_1") (pintype "passive"))
    )
    (net (code "42") (name "Net-(T1-B)") (class "Default")
      (node (ref "R31") (pin "1") (pinfunction "1_1") (pintype "passive"))
      (node (ref "T1") (pin "2") (pinfunction "B_2") (pintype "passive"))
    )
    (net (code "43") (name "Net-(T2-B)") (class "Default")
      (node (ref "R36") (pin "1") (pinfunction "1_1") (pintype "passive"))
      (node (ref "T2") (pin "2") (pinfunction "B_2") (pintype "passive"))
    )
    (net (code "44") (name "Net-(XBEE-RESET)") (class "Default")
      (node (ref "R2") (pin "1") (pinfunction "1_1") (pintype "passive"))
      (node (ref "XBEE") (pin "5") (pinfunction "RESET_5") (pintype "input"))
    )
    (net (code "45") (name "PWM_MOT1") (class "Default")
      (node (ref "M1") (pin "5") (pinfunction "PWM_IN_5") (pintype "input"))
      (node (ref "NUCLEO") (pin "PB2") (pinfunction "PB2_PB2") (pintype "bidirectional"))
    )
    (net (code "46") (name "PWM_MOT2") (class "Default")
      (node (ref "M2") (pin "5") (pinfunction "PWM_IN_5") (pintype "input"))
      (node (ref "NUCLEO") (pin "PB10") (pinfunction "PB10_PB10") (pintype "bidirectional"))
    )
    (net (code "47") (name "P_ON") (class "Default")
      (node (ref "P_ON") (pin "1") (pinfunction "O_1") (pintype "passive"))
      (node (ref "U$9") (pin "REM") (pinfunction "REM_REM") (pintype "bidirectional"))
    )
    (net (code "48") (name "RX_XBEE") (class "Default")
      (node (ref "NUCLEO") (pin "PC10") (pinfunction "PC10_PC10") (pintype "bidirectional"))
      (node (ref "XBEE") (pin "3") (pinfunction "DIN_3") (pintype "input"))
    )
    (net (code "49") (name "S1") (class "Default")
      (node (ref "NUCLEO") (pin "PA8") (pinfunction "PA8_PA8") (pintype "bidirectional"))
      (node (ref "U$3") (pin "P$1") (pinfunction "S1_P$1") (pintype "passive"))
    )
    (net (code "50") (name "S2") (class "Default")
      (node (ref "NUCLEO") (pin "PA9") (pinfunction "PA9_PA9") (pintype "bidirectional"))
      (node (ref "U$7") (pin "P$1") (pinfunction "S1_P$1") (pintype "passive"))
    )
    (net (code "51") (name "S3") (class "Default")
      (node (ref "NUCLEO") (pin "PA11") (pinfunction "PA11_PA11") (pintype "bidirectional"))
      (node (ref "U$6") (pin "P$1") (pinfunction "S1_P$1") (pintype "passive"))
    )
    (net (code "52") (name "S4") (class "Default")
      (node (ref "NUCLEO") (pin "PB8") (pinfunction "PB8_PB8") (pintype "bidirectional"))
      (node (ref "U$5") (pin "P$1") (pinfunction "S1_P$1") (pintype "passive"))
    )
    (net (code "53") (name "S5") (class "Default")
      (node (ref "NUCLEO") (pin "PB9") (pinfunction "PB9_PB9") (pintype "bidirectional"))
      (node (ref "U$4") (pin "P$1") (pinfunction "S1_P$1") (pintype "passive"))
    )
    (net (code "54") (name "SH1") (class "Default")
      (node (ref "NUCLEO") (pin "PA0") (pinfunction "PA0_PA0") (pintype "bidirectional"))
      (node (ref "R21") (pin "1") (pinfunction "1_1") (pintype "passive"))
      (node (ref "R22") (pin "1") (pinfunction "1_1") (pintype "passive"))
    )
    (net (code "55") (name "SH1_D") (class "Default")
      (node (ref "C3") (pin "2") (pinfunction "C2_2") (pintype "passive"))
      (node (ref "R21") (pin "2") (pinfunction "2_2") (pintype "passive"))
      (node (ref "SHARP_AR_3") (pin "3") (pinfunction "S_3") (pintype "passive"))
    )
    (net (code "56") (name "SH2") (class "Default")
      (node (ref "NUCLEO") (pin "PC4") (pinfunction "PC4_PC4") (pintype "bidirectional"))
      (node (ref "R23") (pin "1") (pinfunction "1_1") (pintype "passive"))
      (node (ref "R24") (pin "1") (pinfunction "1_1") (pintype "passive"))
    )
    (net (code "57") (name "SH2_D") (class "Default")
      (node (ref "C6") (pin "2") (pinfunction "C2_2") (pintype "passive"))
      (node (ref "R23") (pin "2") (pinfunction "2_2") (pintype "passive"))
      (node (ref "SHARP_AR_2") (pin "3") (pinfunction "S_3") (pintype "passive"))
    )
    (net (code "58") (name "SH3") (class "Default")
      (node (ref "NUCLEO") (pin "PA2") (pinfunction "PA2_PA2") (pintype "bidirectional"))
      (node (ref "R13") (pin "2") (pinfunction "2_2") (pintype "passive"))
      (node (ref "R14") (pin "1") (pinfunction "1_1") (pintype "passive"))
    )
    (net (code "59") (name "SH3_D") (class "Default")
      (node (ref "C7") (pin "2") (pinfunction "C2_2") (pintype "passive"))
      (node (ref "R14") (pin "2") (pinfunction "2_2") (pintype "passive"))
      (node (ref "SHARP_AR_1") (pin "3") (pinfunction "S_3") (pintype "passive"))
    )
    (net (code "60") (name "SH4") (class "Default")
      (node (ref "NUCLEO") (pin "PA3") (pinfunction "PA3_PA3") (pintype "bidirectional"))
      (node (ref "R25") (pin "1") (pinfunction "1_1") (pintype "passive"))
      (node (ref "R26") (pin "1") (pinfunction "1_1") (pintype "passive"))
    )
    (net (code "61") (name "SH4_D") (class "Default")
      (node (ref "C4") (pin "2") (pinfunction "C2_2") (pintype "passive"))
      (node (ref "R25") (pin "2") (pinfunction "2_2") (pintype "passive"))
      (node (ref "SHARP_AV_3") (pin "3") (pinfunction "S_3") (pintype "passive"))
    )
    (net (code "62") (name "SH5") (class "Default")
      (node (ref "NUCLEO") (pin "PA4") (pinfunction "PA4_PA4") (pintype "bidirectional"))
      (node (ref "R27") (pin "1") (pinfunction "1_1") (pintype "passive"))
      (node (ref "R28") (pin "1") (pinfunction "1_1") (pintype "passive"))
    )
    (net (code "63") (name "SH5_D") (class "Default")
      (node (ref "C5") (pin "2") (pinfunction "C2_2") (pintype "passive"))
      (node (ref "R27") (pin "2") (pinfunction "2_2") (pintype "passive"))
      (node (ref "SHAPR_AV_2") (pin "3") (pinfunction "S_3") (pintype "passive"))
    )
    (net (code "64") (name "SH6") (class "Default")
      (node (ref "NUCLEO") (pin "PA5") (pinfunction "PA5_PA5") (pintype "bidirectional"))
      (node (ref "R29") (pin "1") (pinfunction "1_1") (pintype "passive"))
      (node (ref "R30") (pin "1") (pinfunction "1_1") (pintype "passive"))
    )
    (net (code "65") (name "SH6_D") (class "Default")
      (node (ref "C8") (pin "2") (pinfunction "C2_2") (pintype "passive"))
      (node (ref "R29") (pin "2") (pinfunction "2_2") (pintype "passive"))
      (node (ref "SHARP_AV_1") (pin "3") (pinfunction "S_3") (pintype "passive"))
    )
    (net (code "66") (name "SP") (class "Default")
      (node (ref "NUCLEO") (pin "PA10") (pinfunction "PA10_PA10") (pintype "bidirectional"))
      (node (ref "U$2") (pin "P$1") (pinfunction "S1_P$1") (pintype "passive"))
    )
    (net (code "67") (name "SW1") (class "Default")
      (node (ref "C9") (pin "2") (pinfunction "C2_2") (pintype "passive"))
      (node (ref "NUCLEO") (pin "PA6") (pinfunction "PA6_PA6") (pintype "bidirectional"))
      (node (ref "R4") (pin "1") (pinfunction "1_1") (pintype "passive"))
      (node (ref "X1") (pin "2") (pinfunction "S_2") (pintype "passive"))
    )
    (net (code "68") (name "SW2") (class "Default")
      (node (ref "C10") (pin "2") (pinfunction "C2_2") (pintype "passive"))
      (node (ref "NUCLEO") (pin "PA7") (pinfunction "PA7_PA7") (pintype "bidirectional"))
      (node (ref "R6") (pin "1") (pinfunction "1_1") (pintype "passive"))
      (node (ref "X2") (pin "2") (pinfunction "S_2") (pintype "passive"))
    )
    (net (code "69") (name "SW3") (class "Default")
      (node (ref "C12") (pin "2") (pinfunction "C2_2") (pintype "passive"))
      (node (ref "NUCLEO") (pin "PC1") (pinfunction "PC1_PC1") (pintype "bidirectional"))
      (node (ref "R7") (pin "1") (pinfunction "1_1") (pintype "passive"))
      (node (ref "X3") (pin "2") (pinfunction "S_2") (pintype "passive"))
    )
    (net (code "70") (name "SW4") (class "Default")
      (node (ref "C16") (pin "2") (pinfunction "C2_2") (pintype "passive"))
      (node (ref "NUCLEO") (pin "PB3") (pinfunction "PB3_PB3") (pintype "bidirectional"))
      (node (ref "R8") (pin "1") (pinfunction "1_1") (pintype "passive"))
      (node (ref "X4") (pin "2") (pinfunction "S_2") (pintype "passive"))
    )
    (net (code "71") (name "SW5") (class "Default")
      (node (ref "C13") (pin "2") (pinfunction "C2_2") (pintype "passive"))
      (node (ref "NUCLEO") (pin "PB5") (pinfunction "PB5_PB5") (pintype "bidirectional"))
      (node (ref "R9") (pin "1") (pinfunction "1_1") (pintype "passive"))
      (node (ref "X5") (pin "2") (pinfunction "S_2") (pintype "passive"))
    )
    (net (code "72") (name "SW6") (class "Default")
      (node (ref "C11") (pin "2") (pinfunction "C2_2") (pintype "passive"))
      (node (ref "NUCLEO") (pin "PB4") (pinfunction "PB4_PB4") (pintype "bidirectional"))
      (node (ref "R10") (pin "1") (pinfunction "1_1") (pintype "passive"))
      (node (ref "X6") (pin "2") (pinfunction "S_2") (pintype "passive"))
    )
    (net (code "73") (name "SW7") (class "Default")
      (node (ref "C14") (pin "2") (pinfunction "C2_2") (pintype "passive"))
      (node (ref "NUCLEO") (pin "PC0") (pinfunction "PC0_PC0") (pintype "bidirectional"))
      (node (ref "R11") (pin "1") (pinfunction "1_1") (pintype "passive"))
      (node (ref "X7") (pin "2") (pinfunction "S_2") (pintype "passive"))
    )
    (net (code "74") (name "SW8") (class "Default")
      (node (ref "C15") (pin "2") (pinfunction "C2_2") (pintype "passive"))
      (node (ref "NUCLEO") (pin "PC3") (pinfunction "PC3_PC3") (pintype "bidirectional"))
      (node (ref "R12") (pin "1") (pinfunction "1_1") (pintype "passive"))
      (node (ref "X8") (pin "2") (pinfunction "S_2") (pintype "passive"))
    )
    (net (code "75") (name "SW9") (class "Default")
      (node (ref "C17") (pin "2") (pinfunction "C2_2") (pintype "passive"))
      (node (ref "NUCLEO") (pin "PC2") (pinfunction "PC2_PC2") (pintype "bidirectional"))
      (node (ref "R15") (pin "1") (pinfunction "1_1") (pintype "passive"))
      (node (ref "X9") (pin "2") (pinfunction "S_2") (pintype "passive"))
    )
    (net (code "76") (name "TX_XBEE") (class "Default")
      (node (ref "NUCLEO") (pin "PC11") (pinfunction "PC11_PC11") (pintype "bidirectional"))
      (node (ref "XBEE") (pin "2") (pinfunction "DOUT_2") (pintype "output"))
    )
    (net (code "77") (name "VCC") (class "Default")
      (node (ref "C31") (pin "2") (pinfunction "C2_2") (pintype "passive"))
      (node (ref "COL") (pin "1") (pinfunction "O_1") (pintype "passive"))
      (node (ref "ENA") (pin "1") (pinfunction "O_1") (pintype "passive"))
      (node (ref "NUCLEO") (pin "3V3") (pinfunction "3V3_3V3") (pintype "bidirectional"))
      (node (ref "R1") (pin "1") (pinfunction "1_1") (pintype "passive"))
      (node (ref "R10") (pin "2") (pinfunction "2_2") (pintype "passive"))
      (node (ref "R11") (pin "2") (pinfunction "2_2") (pintype "passive"))
      (node (ref "R12") (pin "2") (pinfunction "2_2") (pintype "passive"))
      (node (ref "R15") (pin "2") (pinfunction "2_2") (pintype "passive"))
      (node (ref "R19") (pin "2") (pinfunction "2_2") (pintype "passive"))
      (node (ref "R2") (pin "2") (pinfunction "2_2") (pintype "passive"))
      (node (ref "R20") (pin "2") (pinfunction "2_2") (pintype "passive"))
      (node (ref "R4") (pin "2") (pinfunction "2_2") (pintype "passive"))
      (node (ref "R6") (pin "2") (pinfunction "2_2") (pintype "passive"))
      (node (ref "R7") (pin "2") (pinfunction "2_2") (pintype "passive"))
      (node (ref "R8") (pin "2") (pinfunction "2_2") (pintype "passive"))
      (node (ref "R9") (pin "2") (pinfunction "2_2") (pintype "passive"))
      (node (ref "S6") (pin "1") (pinfunction "1_1") (pintype "passive"))
      (node (ref "S6") (pin "2") (pinfunction "2_2") (pintype "passive"))
      (node (ref "S6") (pin "3") (pinfunction "3_3") (pintype "passive"))
      (node (ref "S6") (pin "4") (pinfunction "4_4") (pintype "passive"))
      (node (ref "XBEE") (pin "1") (pinfunction "VDD_1") (pintype "power_in"))
    )
    (net (code "78") (name "unconnected-(ENC1E-S-Pad5)") (class "Default")
      (node (ref "ENC1") (pin "5") (pinfunction "S_5") (pintype "passive"))
    )
    (net (code "79") (name "unconnected-(ENC2E-S-Pad5)") (class "Default")
      (node (ref "ENC2") (pin "5") (pinfunction "S_5") (pintype "passive"))
    )
    (net (code "80") (name "unconnected-(L_ON-S-Pad3)") (class "Default")
      (node (ref "L_ON") (pin "3") (pinfunction "S_3") (pintype "passive"))
    )
    (net (code "81") (name "unconnected-(M1-THERM_OUT-Pad9)") (class "Default")
      (node (ref "M1") (pin "9") (pinfunction "THERM_OUT_9") (pintype "output"))
    )
    (net (code "82") (name "unconnected-(M2-THERM_OUT-Pad9)") (class "Default")
      (node (ref "M2") (pin "9") (pinfunction "THERM_OUT_9") (pintype "output"))
    )
    (net (code "83") (name "unconnected-(NUCLEO-NC-PadNC@1)") (class "Default")
      (node (ref "NUCLEO") (pin "NC@1") (pinfunction "NC_NC@1") (pintype "bidirectional"))
    )
    (net (code "84") (name "unconnected-(NUCLEO-NC-PadNC@3)") (class "Default")
      (node (ref "NUCLEO") (pin "NC@3") (pinfunction "NC_NC@3") (pintype "bidirectional"))
    )
    (net (code "85") (name "unconnected-(NUCLEO-NC-PadNC@4)") (class "Default")
      (node (ref "NUCLEO") (pin "NC@4") (pinfunction "NC_NC@4") (pintype "bidirectional"))
    )
    (net (code "86") (name "unconnected-(NUCLEO-NC-PadNC@5)") (class "Default")
      (node (ref "NUCLEO") (pin "NC@5") (pinfunction "NC_NC@5") (pintype "bidirectional"))
    )
    (net (code "87") (name "unconnected-(NUCLEO-NC-PadNC@6)") (class "Default")
      (node (ref "NUCLEO") (pin "NC@6") (pinfunction "NC_NC@6") (pintype "bidirectional"))
    )
    (net (code "88") (name "unconnected-(NUCLEO-NC-PadNC@7)") (class "Default")
      (node (ref "NUCLEO") (pin "NC@7") (pinfunction "NC_NC@7") (pintype "bidirectional"))
    )
    (net (code "89") (name "unconnected-(NUCLEO-NC-PadNC@8)") (class "Default")
      (node (ref "NUCLEO") (pin "NC@8") (pinfunction "NC_NC@8") (pintype "bidirectional"))
    )
    (net (code "90") (name "unconnected-(NUCLEO-NC3-PadNC@2)") (class "Default")
      (node (ref "NUCLEO") (pin "NC@2") (pinfunction "NC3_NC@2") (pintype "bidirectional"))
    )
    (net (code "91") (name "unconnected-(NUCLEO-Pad5V)") (class "Default")
      (node (ref "NUCLEO") (pin "5V") (pinfunction "5V_5V") (pintype "bidirectional"))
    )
    (net (code "92") (name "unconnected-(NUCLEO-PadAVDD)") (class "Default")
      (node (ref "NUCLEO") (pin "AVDD") (pinfunction "AVDD_AVDD") (pintype "bidirectional"))
    )
    (net (code "93") (name "unconnected-(NUCLEO-PadBOOT0)") (class "Default")
      (node (ref "NUCLEO") (pin "BOOT0") (pinfunction "BOOT0_BOOT0") (pintype "bidirectional"))
    )
    (net (code "94") (name "unconnected-(NUCLEO-PadIOREF)") (class "Default")
      (node (ref "NUCLEO") (pin "IOREF") (pinfunction "IOREF_IOREF") (pintype "bidirectional"))
    )
    (net (code "95") (name "unconnected-(NUCLEO-PadPA12)") (class "Default")
      (node (ref "NUCLEO") (pin "PA12") (pinfunction "PA12_PA12") (pintype "bidirectional"))
    )
    (net (code "96") (name "unconnected-(NUCLEO-PadPA13)") (class "Default")
      (node (ref "NUCLEO") (pin "PA13") (pinfunction "PA13_PA13") (pintype "bidirectional"))
    )
    (net (code "97") (name "unconnected-(NUCLEO-PadPA14)") (class "Default")
      (node (ref "NUCLEO") (pin "PA14") (pinfunction "PA14_PA14") (pintype "bidirectional"))
    )
    (net (code "98") (name "unconnected-(NUCLEO-PadPB12)") (class "Default")
      (node (ref "NUCLEO") (pin "PB12") (pinfunction "PB12_PB12") (pintype "bidirectional"))
    )
    (net (code "99") (name "unconnected-(NUCLEO-PadPB13)") (class "Default")
      (node (ref "NUCLEO") (pin "PB13") (pinfunction "PB13_PB13") (pintype "bidirectional"))
    )
    (net (code "100") (name "unconnected-(NUCLEO-PadPB14)") (class "Default")
      (node (ref "NUCLEO") (pin "PB14") (pinfunction "PB14_PB14") (pintype "bidirectional"))
    )
    (net (code "101") (name "unconnected-(NUCLEO-PadPB15)") (class "Default")
      (node (ref "NUCLEO") (pin "PB15") (pinfunction "PB15_PB15") (pintype "bidirectional"))
    )
    (net (code "102") (name "unconnected-(NUCLEO-PadPC12)") (class "Default")
      (node (ref "NUCLEO") (pin "PC12") (pinfunction "PC12_PC12") (pintype "bidirectional"))
    )
    (net (code "103") (name "unconnected-(NUCLEO-PadPD2)") (class "Default")
      (node (ref "NUCLEO") (pin "PD2") (pinfunction "PD2_PD2") (pintype "bidirectional"))
    )
    (net (code "104") (name "unconnected-(NUCLEO-PadPH0)") (class "Default")
      (node (ref "NUCLEO") (pin "PH0") (pinfunction "PH0_PH0") (pintype "bidirectional"))
    )
    (net (code "105") (name "unconnected-(NUCLEO-PadRESET)") (class "Default")
      (node (ref "NUCLEO") (pin "RESET") (pinfunction "RESET_RESET") (pintype "bidirectional"))
    )
    (net (code "106") (name "unconnected-(NUCLEO-PadU5V)") (class "Default")
      (node (ref "NUCLEO") (pin "U5V") (pinfunction "U5V_U5V") (pintype "bidirectional"))
    )
    (net (code "107") (name "unconnected-(NUCLEO-PadVBAT)") (class "Default")
      (node (ref "NUCLEO") (pin "VBAT") (pinfunction "VBAT_VBAT") (pintype "bidirectional"))
    )
    (net (code "108") (name "unconnected-(NUCLEO-PadVDD)") (class "Default")
      (node (ref "NUCLEO") (pin "VDD") (pinfunction "VDD_VDD") (pintype "bidirectional"))
    )
    (net (code "109") (name "unconnected-(NUCLEO-PadVIN)") (class "Default")
      (node (ref "NUCLEO") (pin "VIN") (pinfunction "VIN_VIN") (pintype "bidirectional"))
    )
    (net (code "110") (name "unconnected-(P_ON-S-Pad3)") (class "Default")
      (node (ref "P_ON") (pin "3") (pinfunction "S_3") (pintype "passive"))
    )
    (net (code "111") (name "unconnected-(U$1-S-Pad3)") (class "Default")
      (node (ref "U$1") (pin "3") (pinfunction "S_3") (pintype "passive"))
    )
    (net (code "112") (name "unconnected-(U$9-PadTRIM)") (class "Default")
      (node (ref "U$9") (pin "TRIM") (pinfunction "TRIM_TRIM") (pintype "bidirectional"))
    )
    (net (code "113") (name "unconnected-(XBEE-CTS-Pad12)") (class "Default")
      (node (ref "XBEE") (pin "12") (pinfunction "CTS_12") (pintype "output"))
    )
    (net (code "114") (name "unconnected-(XBEE-DIO0-Pad20)") (class "Default")
      (node (ref "XBEE") (pin "20") (pinfunction "DIO0_20") (pintype "bidirectional"))
    )
    (net (code "115") (name "unconnected-(XBEE-DIO1-Pad19)") (class "Default")
      (node (ref "XBEE") (pin "19") (pinfunction "DIO1_19") (pintype "bidirectional"))
    )
    (net (code "116") (name "unconnected-(XBEE-DIO2-Pad18)") (class "Default")
      (node (ref "XBEE") (pin "18") (pinfunction "DIO2_18") (pintype "bidirectional"))
    )
    (net (code "117") (name "unconnected-(XBEE-DIO3-Pad17)") (class "Default")
      (node (ref "XBEE") (pin "17") (pinfunction "DIO3_17") (pintype "bidirectional"))
    )
    (net (code "118") (name "unconnected-(XBEE-DIO4-Pad11)") (class "Default")
      (node (ref "XBEE") (pin "11") (pinfunction "DIO4_11") (pintype "bidirectional"))
    )
    (net (code "119") (name "unconnected-(XBEE-DIO5-Pad15)") (class "Default")
      (node (ref "XBEE") (pin "15") (pinfunction "DIO5_15") (pintype "bidirectional"))
    )
    (net (code "120") (name "unconnected-(XBEE-DIO9-Pad13)") (class "Default")
      (node (ref "XBEE") (pin "13") (pinfunction "DIO9_13") (pintype "bidirectional"))
    )
    (net (code "121") (name "unconnected-(XBEE-DIO11-Pad7)") (class "Default")
      (node (ref "XBEE") (pin "7") (pinfunction "DIO11_7") (pintype "bidirectional"))
    )
    (net (code "122") (name "unconnected-(XBEE-DIO12-Pad4)") (class "Default")
      (node (ref "XBEE") (pin "4") (pinfunction "DIO12_4") (pintype "bidirectional"))
    )
    (net (code "123") (name "unconnected-(XBEE-DTR-Pad9)") (class "Default")
      (node (ref "XBEE") (pin "9") (pinfunction "DTR_9") (pintype "bidirectional"))
    )
    (net (code "124") (name "unconnected-(XBEE-RES-Pad8)") (class "Default")
      (node (ref "XBEE") (pin "8") (pinfunction "RES_8") (pintype "bidirectional"))
    )
    (net (code "125") (name "unconnected-(XBEE-RES-Pad14)") (class "Default")
      (node (ref "XBEE") (pin "14") (pinfunction "RES_14") (pintype "bidirectional"))
    )
    (net (code "126") (name "unconnected-(XBEE-RSSI-Pad6)") (class "Default")
      (node (ref "XBEE") (pin "6") (pinfunction "RSSI_6") (pintype "bidirectional"))
    )
    (net (code "127") (name "unconnected-(XBEE-RTS-Pad16)") (class "Default")
      (node (ref "XBEE") (pin "16") (pinfunction "RTS_16") (pintype "input"))
    )
  )
)
